# Sheet1.net
KiCad netlist of a schematic drawn in Altium Designer
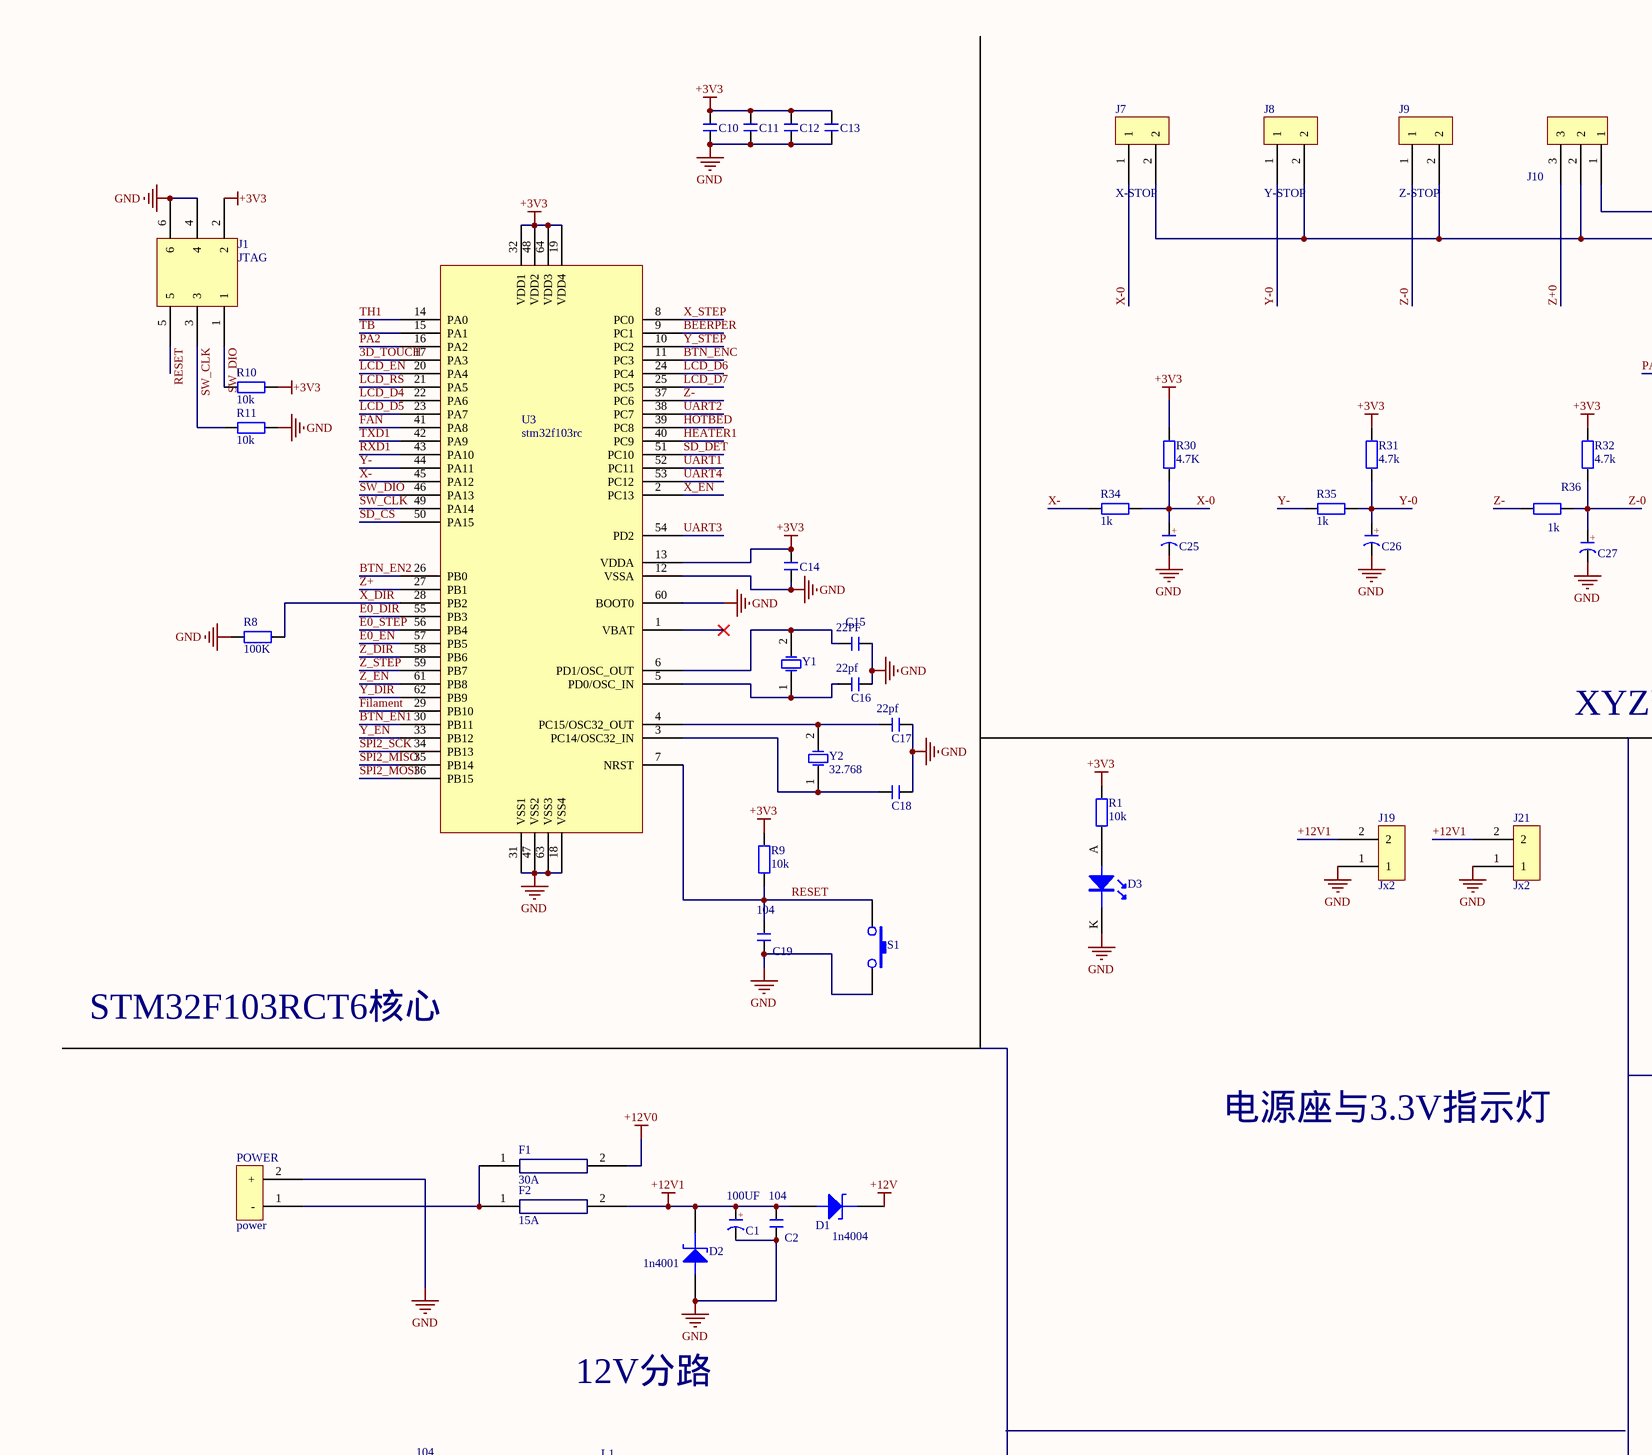
[diagram p0: Sheet1.SchDoc, top left]
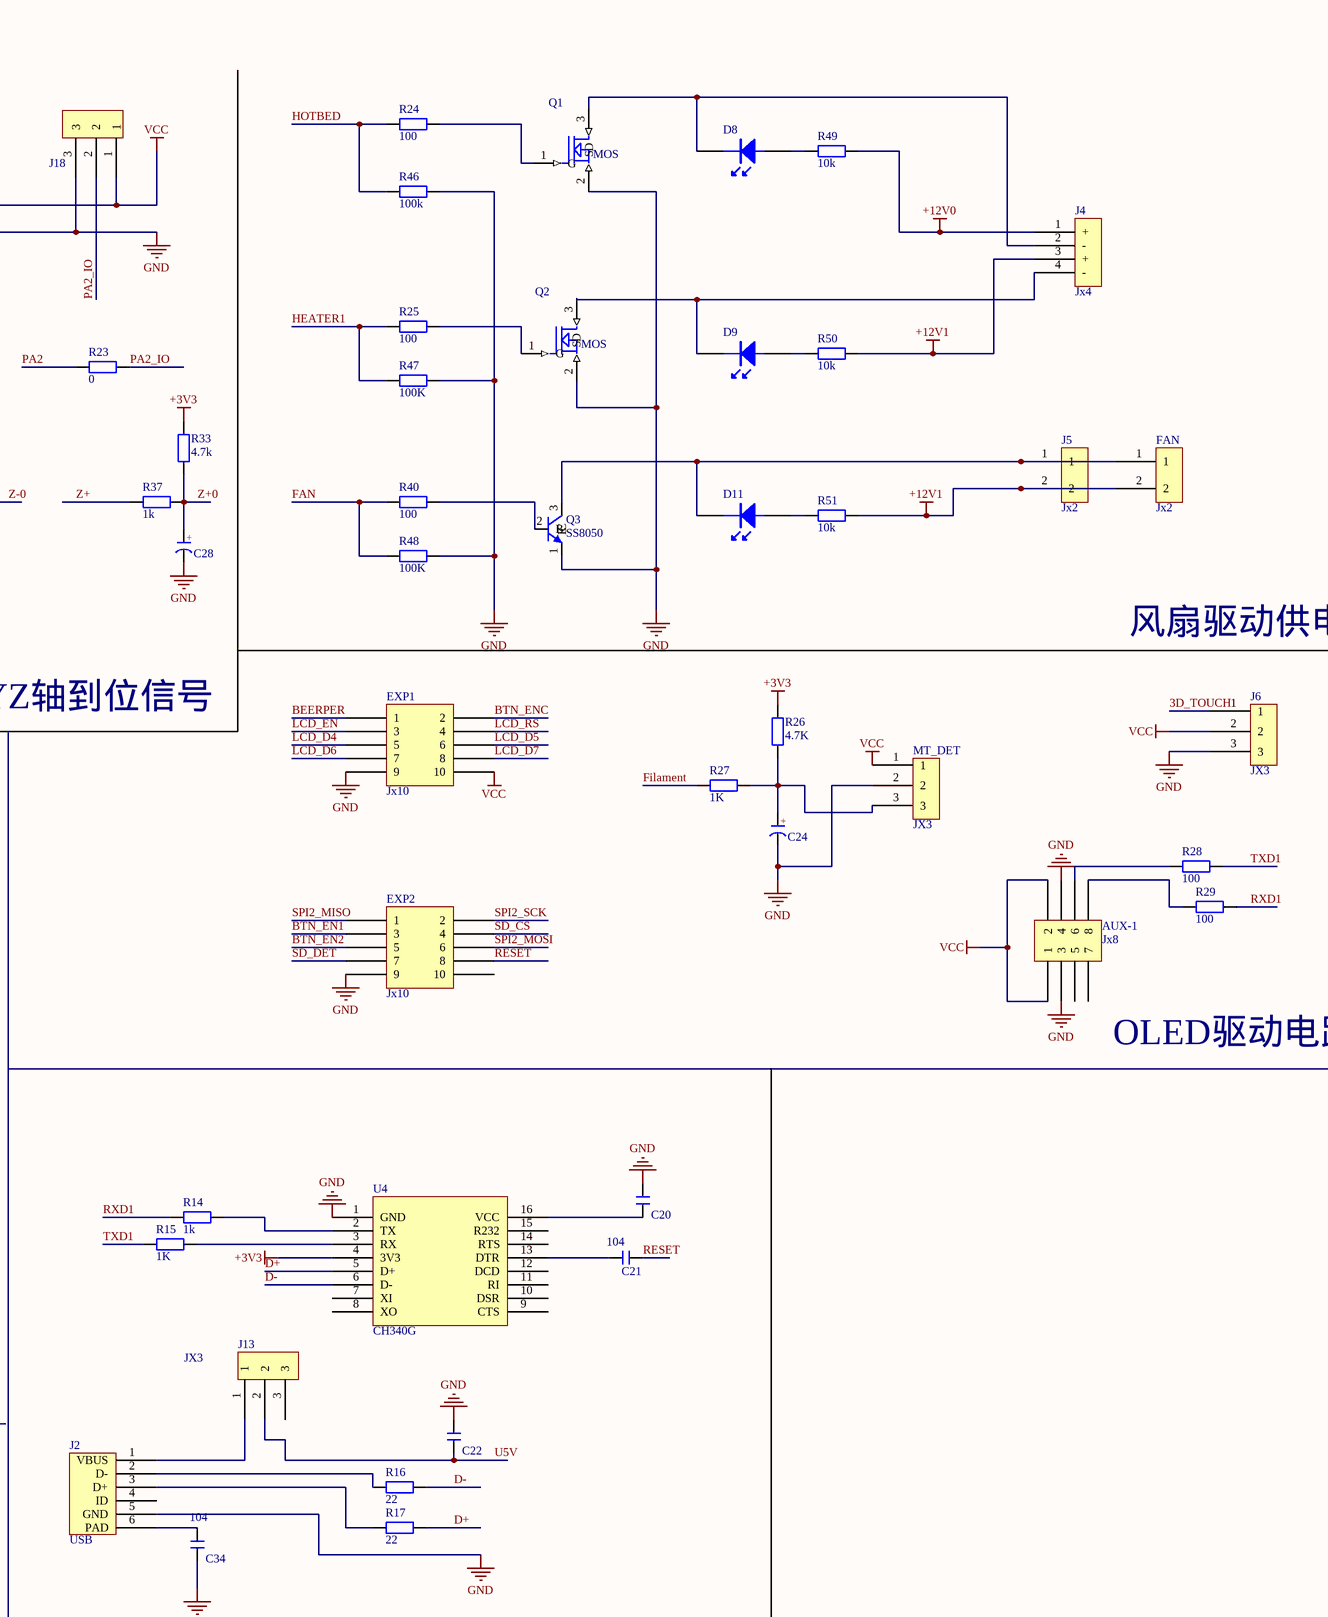
[diagram p1: Sheet1.SchDoc, top middle]
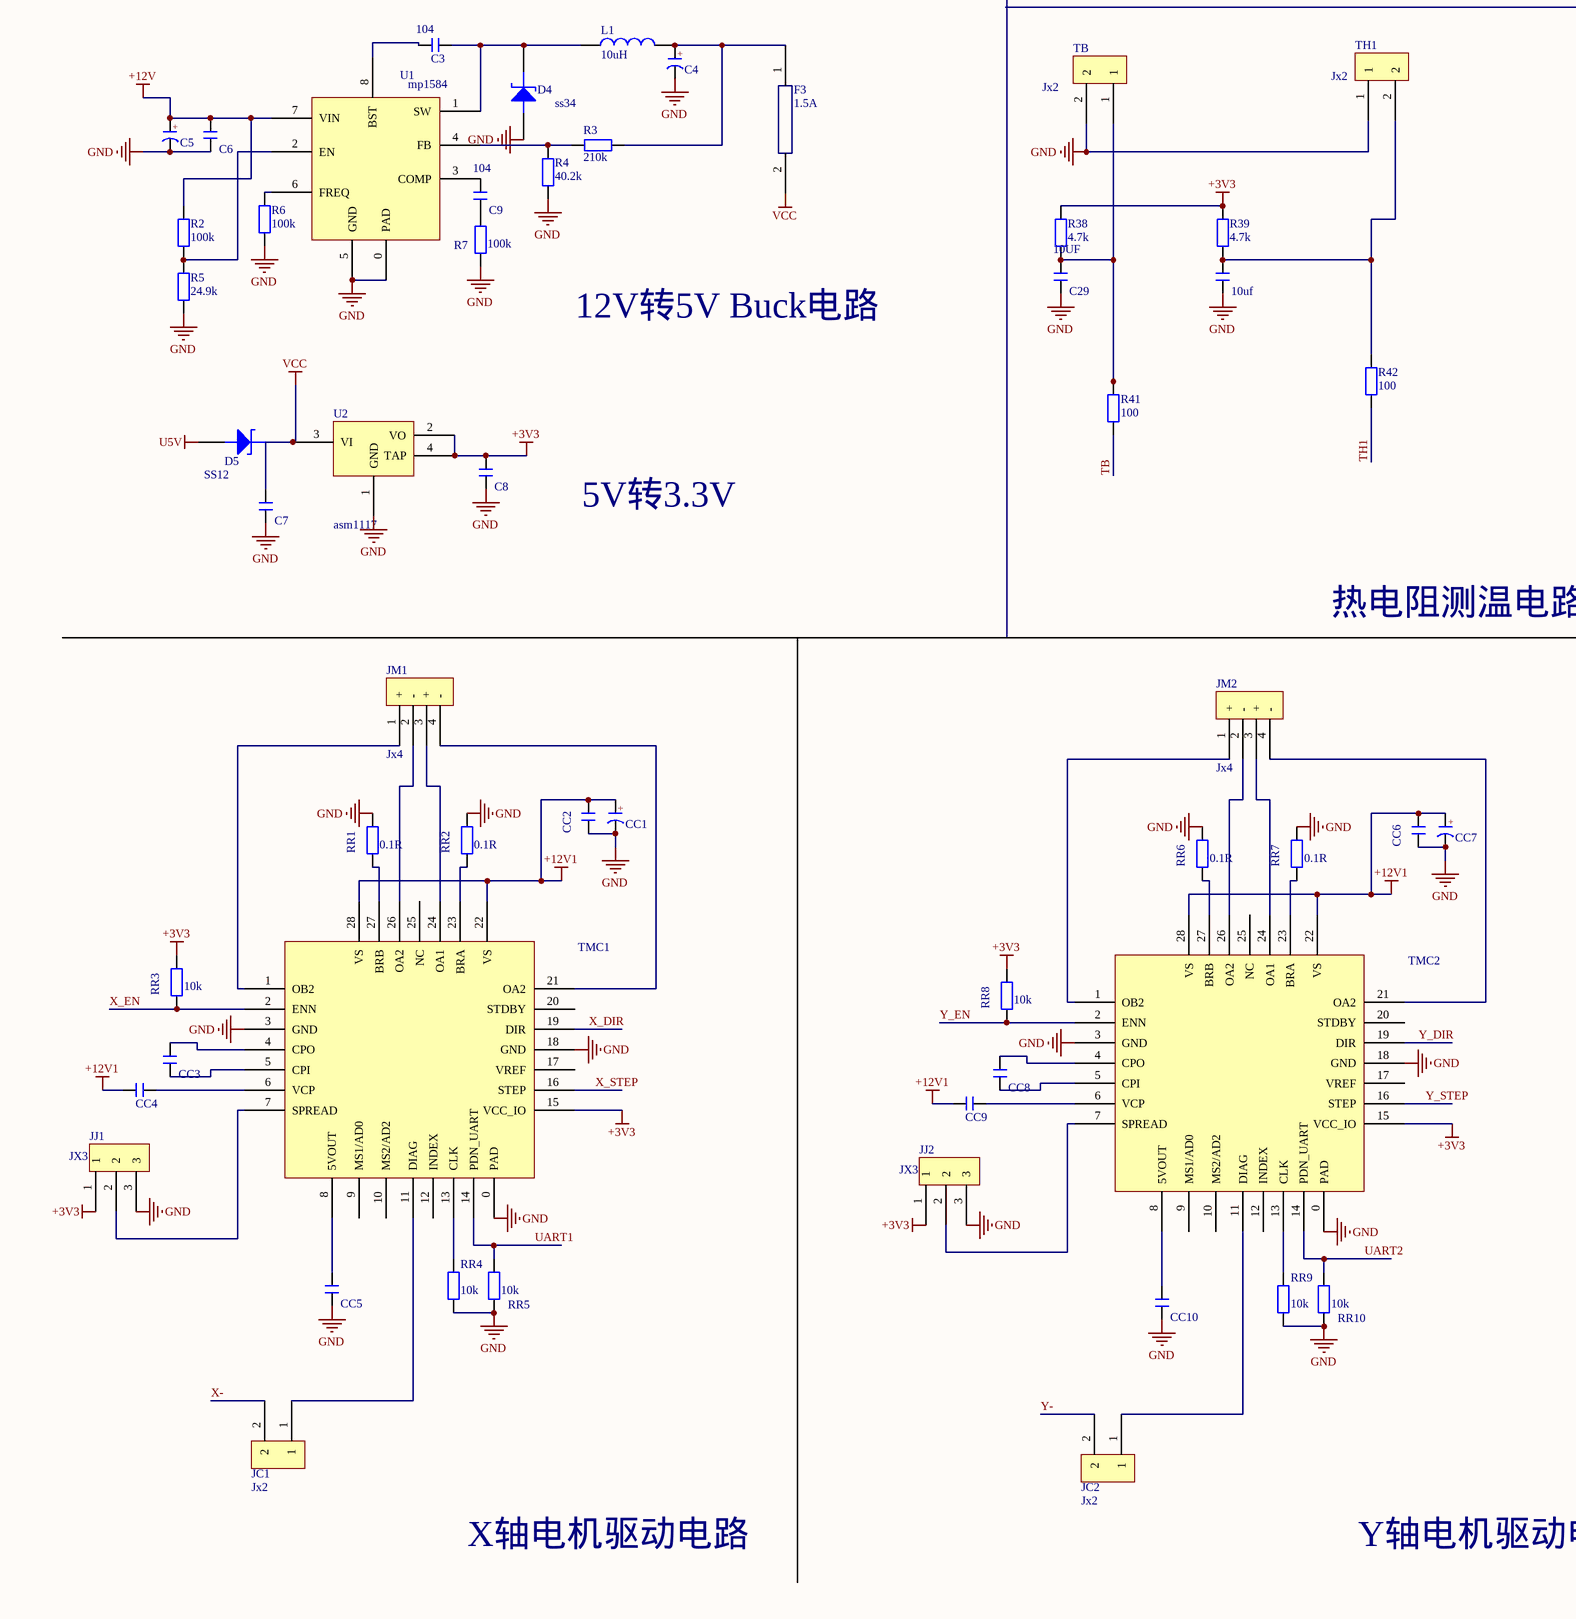
[diagram p2: Sheet1.SchDoc, bottom left]
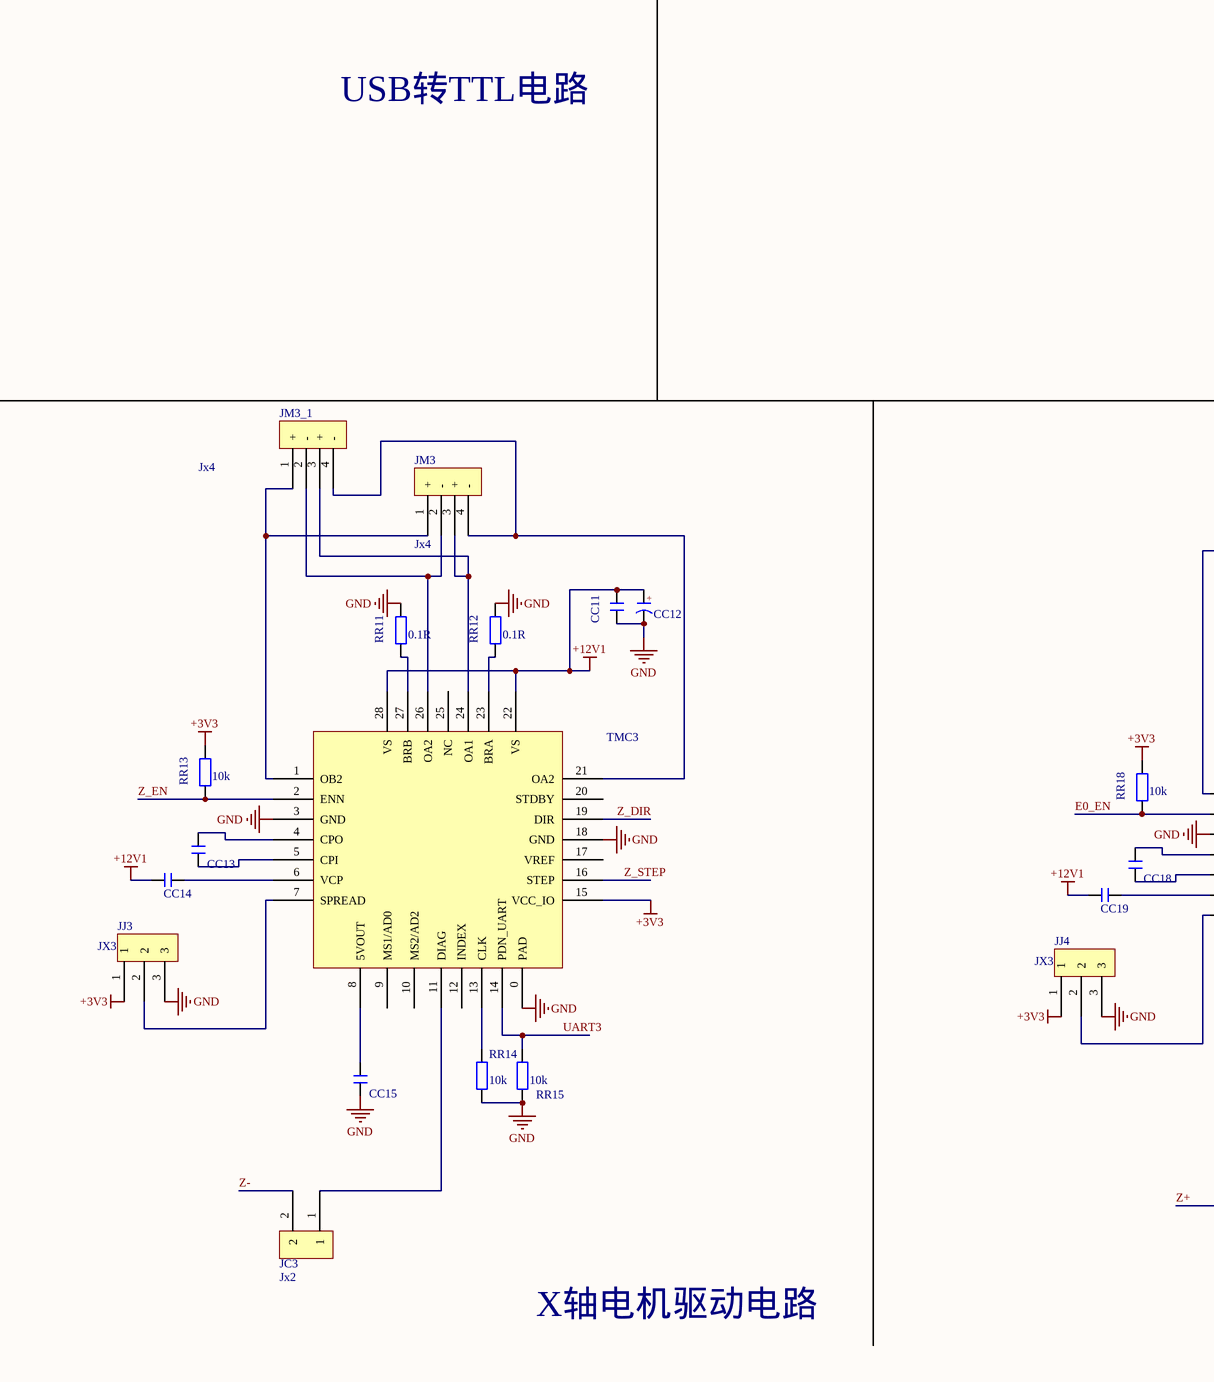
[diagram p3: Sheet1.SchDoc, bottom middle]
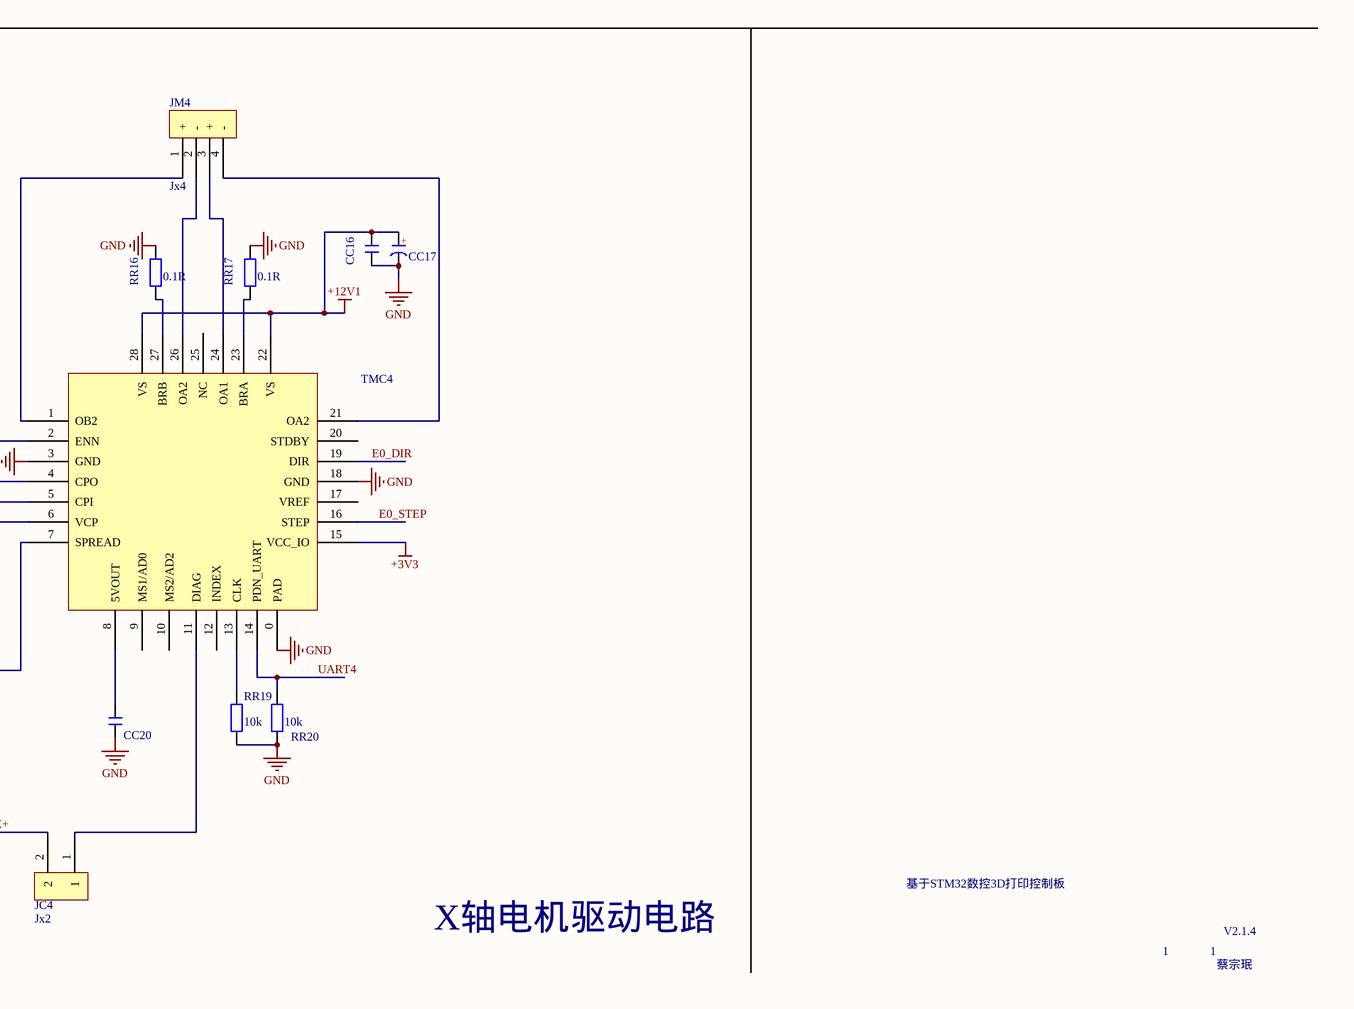
[diagram p4: Sheet1.SchDoc, bottom right]

(export (version "E")
  (design (tool "Eeschema 10.0.6"))
  (components
    (comp (ref "10uf")
      (value "104")
      (footprint "C 0603_M")
      (description "无极性贴片电容")
      (fields (field (name "版权归属") "源创客"))
      (libsource (lib "3.1   - 电阻-电容-电感") (part "C"))
    )
    (comp (ref "AUX-1") (value "Jx8") (footprint "IDC_8P") (libsource (lib "Schlib1") (part "Jx8")))
    (comp (ref "C1")
      (value "100UF")
      (footprint "CS 3.5*8*8 - C")
      (description "贴片电解电容")
      (fields (field (name "版权归属") "源创客"))
      (libsource (lib "3.1   - 电阻-电容-电感") (part "C-CM"))
    )
    (comp (ref "C2")
      (value "104")
      (footprint "C 0603_M")
      (description "无极性贴片电容")
      (fields (field (name "版权归属") "源创客"))
      (libsource (lib "3.1   - 电阻-电容-电感") (part "C"))
    )
    (comp (ref "C3")
      (value "104")
      (footprint "C 0603_M")
      (description "无极性贴片电容")
      (fields (field (name "版权归属") "源创客"))
      (libsource (lib "3.1   - 电阻-电容-电感") (part "C"))
    )
    (comp (ref "C4")
      (value "220uf")
      (footprint "CS 3.5*8*8 - C")
      (description "贴片电解电容")
      (fields (field (name "版权归属") "源创客"))
      (libsource (lib "3.1   - 电阻-电容-电感") (part "C-CM"))
    )
    (comp (ref "C5")
      (value "10uF/10V")
      (footprint "CS 3.5*8*8 - C")
      (description "贴片电解电容")
      (fields (field (name "版权归属") "源创客"))
      (libsource (lib "3.1   - 电阻-电容-电感") (part "C-CM"))
    )
    (comp (ref "C6")
      (value "104")
      (footprint "C 0603_M")
      (description "无极性贴片电容")
      (fields (field (name "版权归属") "源创客"))
      (libsource (lib "3.1   - 电阻-电容-电感") (part "C"))
    )
    (comp (ref "C7")
      (value "10uf")
      (footprint "C 0603_M")
      (description "无极性贴片电容")
      (fields (field (name "版权归属") "源创客"))
      (libsource (lib "3.1   - 电阻-电容-电感") (part "C"))
    )
    (comp (ref "C8")
      (value "10uf")
      (footprint "C 0603_M")
      (description "无极性贴片电容")
      (fields (field (name "版权归属") "源创客"))
      (libsource (lib "3.1   - 电阻-电容-电感") (part "C"))
    )
    (comp (ref "C9")
      (value "104")
      (footprint "C 0603_M")
      (description "无极性贴片电容")
      (fields (field (name "版权归属") "源创客"))
      (libsource (lib "3.1   - 电阻-电容-电感") (part "C"))
    )
    (comp (ref "C10")
      (value "104")
      (footprint "C 0603_M")
      (description "无极性贴片电容")
      (fields (field (name "版权归属") "源创客"))
      (libsource (lib "3.1   - 电阻-电容-电感") (part "C"))
    )
    (comp (ref "C11")
      (value "104")
      (footprint "C 0603_M")
      (description "无极性贴片电容")
      (fields (field (name "版权归属") "源创客"))
      (libsource (lib "3.1   - 电阻-电容-电感") (part "C"))
    )
    (comp (ref "C12")
      (value "104")
      (footprint "C 0603_M")
      (description "无极性贴片电容")
      (fields (field (name "版权归属") "源创客"))
      (libsource (lib "3.1   - 电阻-电容-电感") (part "C"))
    )
    (comp (ref "C13")
      (value "104")
      (footprint "C 0603_M")
      (description "无极性贴片电容")
      (fields (field (name "版权归属") "源创客"))
      (libsource (lib "3.1   - 电阻-电容-电感") (part "C"))
    )
    (comp (ref "C14")
      (value "104")
      (footprint "C 0603_M")
      (description "无极性贴片电容")
      (fields (field (name "版权归属") "源创客"))
      (libsource (lib "3.1   - 电阻-电容-电感") (part "C"))
    )
    (comp (ref "C15")
      (value "22PF")
      (footprint "C 0603_M")
      (description "无极性贴片电容")
      (fields (field (name "版权归属") "源创客"))
      (libsource (lib "3.1   - 电阻-电容-电感") (part "C"))
    )
    (comp (ref "C16")
      (value "22pf")
      (footprint "C 0603_M")
      (description "无极性贴片电容")
      (fields (field (name "版权归属") "源创客"))
      (libsource (lib "3.1   - 电阻-电容-电感") (part "C"))
    )
    (comp (ref "C17")
      (value "22pf")
      (footprint "C 0603_M")
      (description "无极性贴片电容")
      (fields (field (name "版权归属") "源创客"))
      (libsource (lib "3.1   - 电阻-电容-电感") (part "C"))
    )
    (comp (ref "C18")
      (value "22pf")
      (footprint "C 0603_M")
      (description "无极性贴片电容")
      (fields (field (name "版权归属") "源创客"))
      (libsource (lib "3.1   - 电阻-电容-电感") (part "C"))
    )
    (comp (ref "C19")
      (value "104")
      (footprint "C 0603_M")
      (description "无极性贴片电容")
      (fields (field (name "版权归属") "源创客"))
      (libsource (lib "3.1   - 电阻-电容-电感") (part "C"))
    )
    (comp (ref "C20")
      (value "104")
      (footprint "C 0603_M")
      (description "无极性贴片电容")
      (fields (field (name "版权归属") "源创客"))
      (libsource (lib "3.1   - 电阻-电容-电感") (part "C"))
    )
    (comp (ref "C21")
      (value "104")
      (footprint "C 0603_M")
      (description "无极性贴片电容")
      (fields (field (name "版权归属") "源创客"))
      (libsource (lib "3.1   - 电阻-电容-电感") (part "C"))
    )
    (comp (ref "C22")
      (value "104")
      (footprint "C 0603_M")
      (description "无极性贴片电容")
      (fields (field (name "版权归属") "源创客"))
      (libsource (lib "3.1   - 电阻-电容-电感") (part "C"))
    )
    (comp (ref "C24")
      (value "10uF/10V")
      (footprint "C 0603_M")
      (description "贴片电解电容")
      (fields (field (name "版权归属") "源创客"))
      (libsource (lib "3.1   - 电阻-电容-电感") (part "C-CM"))
    )
    (comp (ref "C25")
      (value "10uF/10V")
      (footprint "C 0603_M")
      (description "贴片电解电容")
      (fields (field (name "版权归属") "源创客"))
      (libsource (lib "3.1   - 电阻-电容-电感") (part "C-CM"))
    )
    (comp (ref "C26")
      (value "10uF/10V")
      (footprint "C 0603_M")
      (description "贴片电解电容")
      (fields (field (name "版权归属") "源创客"))
      (libsource (lib "3.1   - 电阻-电容-电感") (part "C-CM"))
    )
    (comp (ref "C27")
      (value "10uF/10V")
      (footprint "C 0603_M")
      (description "贴片电解电容")
      (fields (field (name "版权归属") "源创客"))
      (libsource (lib "3.1   - 电阻-电容-电感") (part "C-CM"))
    )
    (comp (ref "C28")
      (value "10uF/10V")
      (footprint "C 0603_M")
      (description "贴片电解电容")
      (fields (field (name "版权归属") "源创客"))
      (libsource (lib "3.1   - 电阻-电容-电感") (part "C-CM"))
    )
    (comp (ref "C29")
      (value "10UF")
      (footprint "C 0603_M")
      (description "无极性贴片电容")
      (fields (field (name "版权归属") "源创客"))
      (libsource (lib "3.1   - 电阻-电容-电感") (part "C"))
    )
    (comp (ref "C34")
      (value "104")
      (footprint "C 0603_M")
      (description "无极性贴片电容")
      (fields (field (name "版权归属") "源创客"))
      (libsource (lib "3.1   - 电阻-电容-电感") (part "C"))
    )
    (comp (ref "CC1")
      (value "10uF/10V")
      (footprint "C 1206_M")
      (description "贴片电解电容")
      (fields (field (name "版权归属") "源创客"))
      (libsource (lib "3.1   - 电阻-电容-电感") (part "C-CM"))
    )
    (comp (ref "CC2")
      (value "104")
      (footprint "C 0603_M")
      (description "无极性贴片电容")
      (fields (field (name "版权归属") "源创客"))
      (libsource (lib "3.1   - 电阻-电容-电感") (part "C"))
    )
    (comp (ref "CC3")
      (value "104")
      (footprint "C 0603_M")
      (description "无极性贴片电容")
      (fields (field (name "版权归属") "源创客"))
      (libsource (lib "3.1   - 电阻-电容-电感") (part "C"))
    )
    (comp (ref "CC4")
      (value "104")
      (footprint "C 0603_M")
      (description "无极性贴片电容")
      (fields (field (name "版权归属") "源创客"))
      (libsource (lib "3.1   - 电阻-电容-电感") (part "C"))
    )
    (comp (ref "CC5")
      (value "104")
      (footprint "C 0603_M")
      (description "无极性贴片电容")
      (fields (field (name "版权归属") "源创客"))
      (libsource (lib "3.1   - 电阻-电容-电感") (part "C"))
    )
    (comp (ref "CC6")
      (value "104")
      (footprint "C 0603_M")
      (description "无极性贴片电容")
      (fields (field (name "版权归属") "源创客"))
      (libsource (lib "3.1   - 电阻-电容-电感") (part "C"))
    )
    (comp (ref "CC7")
      (value "10uF/10V")
      (footprint "C 1206_M")
      (description "贴片电解电容")
      (fields (field (name "版权归属") "源创客"))
      (libsource (lib "3.1   - 电阻-电容-电感") (part "C-CM"))
    )
    (comp (ref "CC8")
      (value "104")
      (footprint "C 0603_M")
      (description "无极性贴片电容")
      (fields (field (name "版权归属") "源创客"))
      (libsource (lib "3.1   - 电阻-电容-电感") (part "C"))
    )
    (comp (ref "CC9")
      (value "104")
      (footprint "C 0603_M")
      (description "无极性贴片电容")
      (fields (field (name "版权归属") "源创客"))
      (libsource (lib "3.1   - 电阻-电容-电感") (part "C"))
    )
    (comp (ref "CC10")
      (value "104")
      (footprint "C 0603_M")
      (description "无极性贴片电容")
      (fields (field (name "版权归属") "源创客"))
      (libsource (lib "3.1   - 电阻-电容-电感") (part "C"))
    )
    (comp (ref "CC11")
      (value "104")
      (footprint "C 0603_M")
      (description "无极性贴片电容")
      (fields (field (name "版权归属") "源创客"))
      (libsource (lib "3.1   - 电阻-电容-电感") (part "C"))
    )
    (comp (ref "CC12")
      (value "10uF/10V")
      (footprint "C 1206_M")
      (description "贴片电解电容")
      (fields (field (name "版权归属") "源创客"))
      (libsource (lib "3.1   - 电阻-电容-电感") (part "C-CM"))
    )
    (comp (ref "CC13")
      (value "104")
      (footprint "C 0603_M")
      (description "无极性贴片电容")
      (fields (field (name "版权归属") "源创客"))
      (libsource (lib "3.1   - 电阻-电容-电感") (part "C"))
    )
    (comp (ref "CC14")
      (value "104")
      (footprint "C 0603_M")
      (description "无极性贴片电容")
      (fields (field (name "版权归属") "源创客"))
      (libsource (lib "3.1   - 电阻-电容-电感") (part "C"))
    )
    (comp (ref "CC15")
      (value "104")
      (footprint "C 0603_M")
      (description "无极性贴片电容")
      (fields (field (name "版权归属") "源创客"))
      (libsource (lib "3.1   - 电阻-电容-电感") (part "C"))
    )
    (comp (ref "CC16")
      (value "104")
      (footprint "C 0603_M")
      (description "无极性贴片电容")
      (fields (field (name "版权归属") "源创客"))
      (libsource (lib "3.1   - 电阻-电容-电感") (part "C"))
    )
    (comp (ref "CC17")
      (value "10uF/10V")
      (footprint "C 1206_M")
      (description "贴片电解电容")
      (fields (field (name "版权归属") "源创客"))
      (libsource (lib "3.1   - 电阻-电容-电感") (part "C-CM"))
    )
    (comp (ref "CC18")
      (value "104")
      (footprint "C 0603_M")
      (description "无极性贴片电容")
      (fields (field (name "版权归属") "源创客"))
      (libsource (lib "3.1   - 电阻-电容-电感") (part "C"))
    )
    (comp (ref "CC19")
      (value "104")
      (footprint "C 0603_M")
      (description "无极性贴片电容")
      (fields (field (name "版权归属") "源创客"))
      (libsource (lib "3.1   - 电阻-电容-电感") (part "C"))
    )
    (comp (ref "CC20")
      (value "104")
      (footprint "C 0603_M")
      (description "无极性贴片电容")
      (fields (field (name "版权归属") "源创客"))
      (libsource (lib "3.1   - 电阻-电容-电感") (part "C"))
    )
    (comp (ref "D1")
      (value "1n4004")
      (footprint "SMA")
      (description "Zener Diode")
      (libsource (lib "二极管") (part "ZENER2"))
    )
    (comp (ref "D2")
      (value "1n4001")
      (footprint "SMA")
      (description "Zener Diode")
      (libsource (lib "二极管") (part "ZENER2"))
    )
    (comp (ref "D3") (value "发光二极管") (footprint "myLed0805") (libsource (lib "") (part "发光二极管_1")))
    (comp (ref "D4")
      (value "ss34")
      (footprint "SMA")
      (description "Zener Diode")
      (libsource (lib "二极管") (part "ZENER2"))
    )
    (comp (ref "D5")
      (value "SS12")
      (footprint "SMA")
      (description "Zener Diode")
      (libsource (lib "二极管") (part "ZENER2"))
    )
    (comp (ref "D8") (value "发光二极管") (footprint "myLed0805") (libsource (lib "二极管") (part "发光二极管")))
    (comp (ref "D9") (value "发光二极管") (footprint "myLed0805") (libsource (lib "二极管") (part "发光二极管")))
    (comp (ref "D11") (value "发光二极管") (footprint "myLed0805") (libsource (lib "二极管") (part "发光二极管")))
    (comp (ref "EXP1") (value "Jx10") (footprint "DC3-10P") (libsource (lib "Schlib1") (part "Jx10")))
    (comp (ref "EXP2") (value "Jx10") (footprint "DC3-10P") (libsource (lib "Schlib1") (part "Jx10")))
    (comp (ref "F1") (value "30A") (footprint "FU 1206") (libsource (lib "Schlib1") (part "fruse")))
    (comp (ref "F2") (value "15A") (footprint "FU 1206") (libsource (lib "Schlib1") (part "fruse")))
    (comp (ref "F3") (value "1.5A") (footprint "FU 1206") (libsource (lib "Schlib1") (part "fruse")))
    (comp (ref "FAN") (value "Jx2") (footprint "my_XH2.54-2") (libsource (lib "") (part "Jx2_1")))
    (comp (ref "J1") (value "JTAG") (footprint "HDR2.54-LI-2x3P") (libsource (lib "Schlib1") (part "J_2X3")))
    (comp (ref "J2") (value "USB") (footprint "myMicrousb") (libsource (lib "Schlib1") (part "USB")))
    (comp (ref "J4") (value "Jx4") (footprint "HX5.08-4L") (libsource (lib "") (part "Jx4_1")))
    (comp (ref "J5") (value "Jx2") (footprint "my_XH2.54-2") (libsource (lib "") (part "Jx2_1")))
    (comp (ref "J6") (value "JX3") (footprint "HDR2.54-LI-3P") (libsource (lib "Schlib1") (part "JX3")))
    (comp (ref "J7") (value "X-STOP") (footprint "my_XH2.54-2") (libsource (lib "Schlib1") (part "Jx2")))
    (comp (ref "J8") (value "Y-STOP") (footprint "my_XH2.54-2") (libsource (lib "Schlib1") (part "Jx2")))
    (comp (ref "J9") (value "Z-STOP") (footprint "my_XH2.54-2") (libsource (lib "Schlib1") (part "Jx2")))
    (comp (ref "J10") (value "JX3") (footprint "XH_3p") (libsource (lib "Schlib1") (part "JX3")))
    (comp (ref "J13") (value "JX3") (footprint "HDR2.54-LI-3P") (libsource (lib "") (part "JX3_1")))
    (comp (ref "J18") (value "JX3") (footprint "XH_3p") (libsource (lib "Schlib1") (part "JX3")))
    (comp (ref "J19") (value "Jx2") (footprint "my_XH2.54-2") (libsource (lib "Schlib1") (part "Jx2")))
    (comp (ref "J21") (value "Jx2") (footprint "my_XH2.54-2") (libsource (lib "Schlib1") (part "Jx2")))
    (comp (ref "JC1") (value "Jx2") (footprint "HDR2.54-LI-2P") (libsource (lib "") (part "Jx2_2")))
    (comp (ref "JC2") (value "Jx2") (footprint "HDR2.54-LI-2P") (libsource (lib "") (part "Jx2_2")))
    (comp (ref "JC3") (value "Jx2") (footprint "HDR2.54-LI-2P") (libsource (lib "") (part "Jx2_2")))
    (comp (ref "JC4") (value "Jx2") (footprint "HDR2.54-LI-2P") (libsource (lib "") (part "Jx2_2")))
    (comp (ref "JJ1") (value "JX3") (footprint "HDR2.54-LI-3P") (libsource (lib "") (part "JX3_1")))
    (comp (ref "JJ2") (value "JX3") (footprint "HDR2.54-LI-3P") (libsource (lib "") (part "JX3_1")))
    (comp (ref "JJ3") (value "JX3") (footprint "HDR2.54-LI-3P") (libsource (lib "") (part "JX3_1")))
    (comp (ref "JJ4") (value "JX3") (footprint "HDR2.54-LI-3P") (libsource (lib "") (part "JX3_1")))
    (comp (ref "JM1") (value "Jx4") (footprint "XH2.54-4") (libsource (lib "Schlib1") (part "Jx4")))
    (comp (ref "JM2") (value "Jx4") (footprint "XH2.54-4") (libsource (lib "Schlib1") (part "Jx4")))
    (comp (ref "JM3") (value "Jx4") (footprint "XH2.54-4") (libsource (lib "Schlib1") (part "Jx4")))
    (comp (ref "JM3_1") (value "Jx4") (footprint "XH2.54-4") (libsource (lib "Schlib1") (part "Jx4")))
    (comp (ref "JM4") (value "Jx4") (footprint "XH2.54-4") (libsource (lib "Schlib1") (part "Jx4")))
    (comp (ref "L1")
      (value "10uH")
      (footprint "CDRH74")
      (description "小功率贴片电感")
      (fields (field (name "版权归属") "源创客"))
      (libsource (lib "3.1   - 电阻-电容-电感") (part "L"))
    )
    (comp (ref "MT_DET") (value "JX3") (footprint "XH_3p") (libsource (lib "Schlib1") (part "JX3")))
    (comp (ref "POWER") (value "power") (footprint "HX5.08-2L") (libsource (lib "Schlib1") (part "power")))
    (comp (ref "Q1") (value "MOS") (footprint "TO252") (libsource (lib "Schlib1") (part "MOS")))
    (comp (ref "Q2") (value "MOS") (footprint "TO252") (libsource (lib "Schlib1") (part "MOS")))
    (comp (ref "Q3")
      (value "SS8050")
      (footprint "SOT23")
      (description "高频放大-NPN型")
      (fields (field (name "版权归属") "源创客"))
      (libsource (lib "6.2   - 三极管") (part "8050-DIP"))
    )
    (comp (ref "R1")
      (value "10k")
      (footprint "R 0603_M")
      (description "电流检测电阻")
      (fields (field (name "版权归属") "源创客"))
      (libsource (lib "3.1   - 电阻-电容-电感") (part "R-I"))
    )
    (comp (ref "R2")
      (value "100k")
      (footprint "R 0603_M")
      (description "电流检测电阻")
      (fields (field (name "版权归属") "源创客"))
      (libsource (lib "3.1   - 电阻-电容-电感") (part "R-I"))
    )
    (comp (ref "R3")
      (value "210k")
      (footprint "R 0603_M")
      (description "电流检测电阻")
      (fields (field (name "版权归属") "源创客"))
      (libsource (lib "3.1   - 电阻-电容-电感") (part "R-I"))
    )
    (comp (ref "R4")
      (value "40.2k")
      (footprint "R 0603_M")
      (description "电流检测电阻")
      (fields (field (name "版权归属") "源创客"))
      (libsource (lib "3.1   - 电阻-电容-电感") (part "R-I"))
    )
    (comp (ref "R5")
      (value "24.9k")
      (footprint "R 0603_M")
      (description "电流检测电阻")
      (fields (field (name "版权归属") "源创客"))
      (libsource (lib "3.1   - 电阻-电容-电感") (part "R-I"))
    )
    (comp (ref "R6")
      (value "100k")
      (footprint "R 0603_M")
      (description "电流检测电阻")
      (fields (field (name "版权归属") "源创客"))
      (libsource (lib "3.1   - 电阻-电容-电感") (part "R-I"))
    )
    (comp (ref "R7")
      (value "100k")
      (footprint "R 0603_M")
      (description "电流检测电阻")
      (fields (field (name "版权归属") "源创客"))
      (libsource (lib "3.1   - 电阻-电容-电感") (part "R-I"))
    )
    (comp (ref "R8")
      (value "100K")
      (footprint "R 0603_M")
      (description "电流检测电阻")
      (fields (field (name "版权归属") "源创客"))
      (libsource (lib "3.1   - 电阻-电容-电感") (part "R-I"))
    )
    (comp (ref "R9")
      (value "10k")
      (footprint "R 0603_M")
      (description "电流检测电阻")
      (fields (field (name "版权归属") "源创客"))
      (libsource (lib "3.1   - 电阻-电容-电感") (part "R-I"))
    )
    (comp (ref "R10")
      (value "10k")
      (footprint "R 0603_M")
      (description "电流检测电阻")
      (fields (field (name "版权归属") "源创客"))
      (libsource (lib "3.1   - 电阻-电容-电感") (part "R-I"))
    )
    (comp (ref "R11")
      (value "10k")
      (footprint "R 0603_M")
      (description "电流检测电阻")
      (fields (field (name "版权归属") "源创客"))
      (libsource (lib "3.1   - 电阻-电容-电感") (part "R-I"))
    )
    (comp (ref "R14")
      (value "1k")
      (footprint "R 0603_M")
      (description "电流检测电阻")
      (fields (field (name "版权归属") "源创客"))
      (libsource (lib "3.1   - 电阻-电容-电感") (part "R-I"))
    )
    (comp (ref "R15")
      (value "1K")
      (footprint "R 0603_M")
      (description "电流检测电阻")
      (fields (field (name "版权归属") "源创客"))
      (libsource (lib "3.1   - 电阻-电容-电感") (part "R-I"))
    )
    (comp (ref "R16")
      (value "22")
      (footprint "R 0603_M")
      (description "电流检测电阻")
      (fields (field (name "版权归属") "源创客"))
      (libsource (lib "3.1   - 电阻-电容-电感") (part "R-I"))
    )
    (comp (ref "R17")
      (value "22")
      (footprint "R 0603_M")
      (description "电流检测电阻")
      (fields (field (name "版权归属") "源创客"))
      (libsource (lib "3.1   - 电阻-电容-电感") (part "R-I"))
    )
    (comp (ref "R23")
      (value "0")
      (footprint "R 0603_M")
      (description "电流检测电阻")
      (fields (field (name "版权归属") "源创客"))
      (libsource (lib "3.1   - 电阻-电容-电感") (part "R-I"))
    )
    (comp (ref "R24")
      (value "100")
      (footprint "R 0603_M")
      (description "电流检测电阻")
      (fields (field (name "版权归属") "源创客"))
      (libsource (lib "3.1   - 电阻-电容-电感") (part "R-I"))
    )
    (comp (ref "R25")
      (value "100")
      (footprint "R 0603_M")
      (description "电流检测电阻")
      (fields (field (name "版权归属") "源创客"))
      (libsource (lib "3.1   - 电阻-电容-电感") (part "R-I"))
    )
    (comp (ref "R26")
      (value "4.7K")
      (footprint "R 0603_M")
      (description "电流检测电阻")
      (fields (field (name "版权归属") "源创客"))
      (libsource (lib "3.1   - 电阻-电容-电感") (part "R-I"))
    )
    (comp (ref "R27")
      (value "1K")
      (footprint "R 0603_M")
      (description "电流检测电阻")
      (fields (field (name "版权归属") "源创客"))
      (libsource (lib "3.1   - 电阻-电容-电感") (part "R-I"))
    )
    (comp (ref "R28")
      (value "100")
      (footprint "R 0603_M")
      (description "电流检测电阻")
      (fields (field (name "版权归属") "源创客"))
      (libsource (lib "3.1   - 电阻-电容-电感") (part "R-I"))
    )
    (comp (ref "R29")
      (value "100")
      (footprint "R 0603_M")
      (description "电流检测电阻")
      (fields (field (name "版权归属") "源创客"))
      (libsource (lib "3.1   - 电阻-电容-电感") (part "R-I"))
    )
    (comp (ref "R30")
      (value "4.7K")
      (footprint "R 0603_M")
      (description "电流检测电阻")
      (fields (field (name "版权归属") "源创客"))
      (libsource (lib "3.1   - 电阻-电容-电感") (part "R-I"))
    )
    (comp (ref "R31")
      (value "4.7k")
      (footprint "R 0603_M")
      (description "电流检测电阻")
      (fields (field (name "版权归属") "源创客"))
      (libsource (lib "3.1   - 电阻-电容-电感") (part "R-I"))
    )
    (comp (ref "R32")
      (value "4.7k")
      (footprint "R 0603_M")
      (description "电流检测电阻")
      (fields (field (name "版权归属") "源创客"))
      (libsource (lib "3.1   - 电阻-电容-电感") (part "R-I"))
    )
    (comp (ref "R33")
      (value "4.7k")
      (footprint "R 0603_M")
      (description "电流检测电阻")
      (fields (field (name "版权归属") "源创客"))
      (libsource (lib "3.1   - 电阻-电容-电感") (part "R-I"))
    )
    (comp (ref "R34")
      (value "1k")
      (footprint "R 0603_M")
      (description "电流检测电阻")
      (fields (field (name "版权归属") "源创客"))
      (libsource (lib "3.1   - 电阻-电容-电感") (part "R-I"))
    )
    (comp (ref "R35")
      (value "1k")
      (footprint "R 0603_M")
      (description "电流检测电阻")
      (fields (field (name "版权归属") "源创客"))
      (libsource (lib "3.1   - 电阻-电容-电感") (part "R-I"))
    )
    (comp (ref "R36")
      (value "1k")
      (footprint "R 0603_M")
      (description "电流检测电阻")
      (fields (field (name "版权归属") "源创客"))
      (libsource (lib "3.1   - 电阻-电容-电感") (part "R-I"))
    )
    (comp (ref "R37")
      (value "1k")
      (footprint "R 0603_M")
      (description "电流检测电阻")
      (fields (field (name "版权归属") "源创客"))
      (libsource (lib "3.1   - 电阻-电容-电感") (part "R-I"))
    )
    (comp (ref "R38")
      (value "4.7k")
      (footprint "R 0603_M")
      (description "电流检测电阻")
      (fields (field (name "版权归属") "源创客"))
      (libsource (lib "3.1   - 电阻-电容-电感") (part "R-I"))
    )
    (comp (ref "R39")
      (value "4.7k")
      (footprint "R 0603_M")
      (description "电流检测电阻")
      (fields (field (name "版权归属") "源创客"))
      (libsource (lib "3.1   - 电阻-电容-电感") (part "R-I"))
    )
    (comp (ref "R40")
      (value "100")
      (footprint "R 0603_M")
      (description "电流检测电阻")
      (fields (field (name "版权归属") "源创客"))
      (libsource (lib "3.1   - 电阻-电容-电感") (part "R-I"))
    )
    (comp (ref "R41")
      (value "100")
      (footprint "R 0603_M")
      (description "电流检测电阻")
      (fields (field (name "版权归属") "源创客"))
      (libsource (lib "3.1   - 电阻-电容-电感") (part "R-I"))
    )
    (comp (ref "R42")
      (value "100")
      (footprint "R 0603_M")
      (description "电流检测电阻")
      (fields (field (name "版权归属") "源创客"))
      (libsource (lib "3.1   - 电阻-电容-电感") (part "R-I"))
    )
    (comp (ref "R46")
      (value "100k")
      (footprint "R 0603_M")
      (description "电流检测电阻")
      (fields (field (name "版权归属") "源创客"))
      (libsource (lib "3.1   - 电阻-电容-电感") (part "R-I"))
    )
    (comp (ref "R47")
      (value "100K")
      (footprint "R 0603_M")
      (description "电流检测电阻")
      (fields (field (name "版权归属") "源创客"))
      (libsource (lib "3.1   - 电阻-电容-电感") (part "R-I"))
    )
    (comp (ref "R48")
      (value "100K")
      (footprint "R 0603_M")
      (description "电流检测电阻")
      (fields (field (name "版权归属") "源创客"))
      (libsource (lib "3.1   - 电阻-电容-电感") (part "R-I"))
    )
    (comp (ref "R49")
      (value "10k")
      (footprint "R 0603_M")
      (description "电流检测电阻")
      (fields (field (name "版权归属") "源创客"))
      (libsource (lib "3.1   - 电阻-电容-电感") (part "R-I"))
    )
    (comp (ref "R50")
      (value "10k")
      (footprint "R 0603_M")
      (description "电流检测电阻")
      (fields (field (name "版权归属") "源创客"))
      (libsource (lib "3.1   - 电阻-电容-电感") (part "R-I"))
    )
    (comp (ref "R51")
      (value "10k")
      (footprint "R 0603_M")
      (description "电流检测电阻")
      (fields (field (name "版权归属") "源创客"))
      (libsource (lib "3.1   - 电阻-电容-电感") (part "R-I"))
    )
    (comp (ref "RR1")
      (value "0.1R")
      (footprint "R 1206_L")
      (description "电流检测电阻")
      (fields (field (name "版权归属") "源创客"))
      (libsource (lib "3.1   - 电阻-电容-电感") (part "R-I"))
    )
    (comp (ref "RR2")
      (value "0.1R")
      (footprint "R 1206_L")
      (description "电流检测电阻")
      (fields (field (name "版权归属") "源创客"))
      (libsource (lib "3.1   - 电阻-电容-电感") (part "R-I"))
    )
    (comp (ref "RR3")
      (value "10k")
      (footprint "R 0603_M")
      (description "电流检测电阻")
      (fields (field (name "版权归属") "源创客"))
      (libsource (lib "3.1   - 电阻-电容-电感") (part "R-I"))
    )
    (comp (ref "RR4")
      (value "10k")
      (footprint "R 0603_M")
      (description "电流检测电阻")
      (fields (field (name "版权归属") "源创客"))
      (libsource (lib "3.1   - 电阻-电容-电感") (part "R-I"))
    )
    (comp (ref "RR5")
      (value "10k")
      (footprint "R 0603_M")
      (description "电流检测电阻")
      (fields (field (name "版权归属") "源创客"))
      (libsource (lib "3.1   - 电阻-电容-电感") (part "R-I"))
    )
    (comp (ref "RR6")
      (value "0.1R")
      (footprint "R 1206_L")
      (description "电流检测电阻")
      (fields (field (name "版权归属") "源创客"))
      (libsource (lib "3.1   - 电阻-电容-电感") (part "R-I"))
    )
    (comp (ref "RR7")
      (value "0.1R")
      (footprint "R 1206_L")
      (description "电流检测电阻")
      (fields (field (name "版权归属") "源创客"))
      (libsource (lib "3.1   - 电阻-电容-电感") (part "R-I"))
    )
    (comp (ref "RR8")
      (value "10k")
      (footprint "R 0603_M")
      (description "电流检测电阻")
      (fields (field (name "版权归属") "源创客"))
      (libsource (lib "3.1   - 电阻-电容-电感") (part "R-I"))
    )
    (comp (ref "RR9")
      (value "10k")
      (footprint "R 0603_M")
      (description "电流检测电阻")
      (fields (field (name "版权归属") "源创客"))
      (libsource (lib "3.1   - 电阻-电容-电感") (part "R-I"))
    )
    (comp (ref "RR10")
      (value "10k")
      (footprint "R 0603_M")
      (description "电流检测电阻")
      (fields (field (name "版权归属") "源创客"))
      (libsource (lib "3.1   - 电阻-电容-电感") (part "R-I"))
    )
    (comp (ref "RR11")
      (value "0.1R")
      (footprint "R 1206_L")
      (description "电流检测电阻")
      (fields (field (name "版权归属") "源创客"))
      (libsource (lib "3.1   - 电阻-电容-电感") (part "R-I"))
    )
    (comp (ref "RR12")
      (value "0.1R")
      (footprint "R 1206_L")
      (description "电流检测电阻")
      (fields (field (name "版权归属") "源创客"))
      (libsource (lib "3.1   - 电阻-电容-电感") (part "R-I"))
    )
    (comp (ref "RR13")
      (value "10k")
      (footprint "R 0603_M")
      (description "电流检测电阻")
      (fields (field (name "版权归属") "源创客"))
      (libsource (lib "3.1   - 电阻-电容-电感") (part "R-I"))
    )
    (comp (ref "RR14")
      (value "10k")
      (footprint "R 0603_M")
      (description "电流检测电阻")
      (fields (field (name "版权归属") "源创客"))
      (libsource (lib "3.1   - 电阻-电容-电感") (part "R-I"))
    )
    (comp (ref "RR15")
      (value "10k")
      (footprint "R 0603_M")
      (description "电流检测电阻")
      (fields (field (name "版权归属") "源创客"))
      (libsource (lib "3.1   - 电阻-电容-电感") (part "R-I"))
    )
    (comp (ref "RR16")
      (value "0.1R")
      (footprint "R 1206_L")
      (description "电流检测电阻")
      (fields (field (name "版权归属") "源创客"))
      (libsource (lib "3.1   - 电阻-电容-电感") (part "R-I"))
    )
    (comp (ref "RR17")
      (value "0.1R")
      (footprint "R 1206_L")
      (description "电流检测电阻")
      (fields (field (name "版权归属") "源创客"))
      (libsource (lib "3.1   - 电阻-电容-电感") (part "R-I"))
    )
    (comp (ref "RR18")
      (value "10k")
      (footprint "R 0603_M")
      (description "电流检测电阻")
      (fields (field (name "版权归属") "源创客"))
      (libsource (lib "3.1   - 电阻-电容-电感") (part "R-I"))
    )
    (comp (ref "RR19")
      (value "10k")
      (footprint "R 0603_M")
      (description "电流检测电阻")
      (fields (field (name "版权归属") "源创客"))
      (libsource (lib "3.1   - 电阻-电容-电感") (part "R-I"))
    )
    (comp (ref "RR20")
      (value "10k")
      (footprint "R 0603_M")
      (description "电流检测电阻")
      (fields (field (name "版权归属") "源创客"))
      (libsource (lib "3.1   - 电阻-电容-电感") (part "R-I"))
    )
    (comp (ref "S1") (value "微动开关") (footprint "TSW SMD-3*6*2.5") (libsource (lib "开关") (part "微动开关")))
    (comp (ref "TB") (value "Jx2") (footprint "my_XH2.54-2") (libsource (lib "") (part "Jx2_1")))
    (comp (ref "TH1") (value "Jx2") (footprint "my_XH2.54-2") (libsource (lib "Schlib1") (part "Jx2")))
    (comp (ref "TMC1") (value "TMC2208") (footprint "my_2208") (libsource (lib "Schlib1") (part "TMC2208")))
    (comp (ref "TMC2") (value "TMC2208") (footprint "my_2208") (libsource (lib "Schlib1") (part "TMC2208")))
    (comp (ref "TMC3") (value "TMC2208") (footprint "my_2208") (libsource (lib "Schlib1") (part "TMC2208")))
    (comp (ref "TMC4") (value "TMC2208") (footprint "my_2208") (libsource (lib "Schlib1") (part "TMC2208")))
    (comp (ref "U1") (value "mp1584") (footprint "MP1584EN") (libsource (lib "Schlib1") (part "mp1584")))
    (comp (ref "U2") (value "asm1117") (footprint "SOT-223") (libsource (lib "Schlib1") (part "asm1117")))
    (comp (ref "U3")
      (value "stm32f103rc")
      (footprint "LQFP64_M")
      (libsource (lib "Schlib1") (part "STM32_F103RC"))
    )
    (comp (ref "U4") (value "CH340G") (footprint "SOP16") (libsource (lib "Schlib1") (part "CH340G")))
    (comp (ref "Y1")
      (value "8MHz")
      (footprint "OSC HC-49S")
      (description "Crystal Oscillator")
      (fields (field (name "PUBLISHER") "Altium Limited"))
      (libsource (lib "WarShip V3 STM32103封装库") (part "XTAL"))
    )
    (comp (ref "Y2")
      (value "32.768")
      (footprint "OSC-3x8-LI")
      (description "Crystal Oscillator")
      (fields (field (name "PUBLISHER") "Altium Limited"))
      (libsource (lib "WarShip V3 STM32103封装库") (part "XTAL"))
    )
  )
  (nets
    (net (code "1") (name "+3V3") (class "Default")
      (node (ref "C10") (pin "2") (pinfunction "2_2") (pintype "passive"))
      (node (ref "C11") (pin "2") (pinfunction "2_2") (pintype "passive"))
      (node (ref "C12") (pin "2") (pinfunction "2_2") (pintype "passive"))
      (node (ref "C13") (pin "2") (pinfunction "2_2") (pintype "passive"))
      (node (ref "C14") (pin "2") (pinfunction "2_2") (pintype "passive"))
      (node (ref "C8") (pin "1") (pinfunction "1_1") (pintype "passive"))
      (node (ref "J1") (pin "2") (pinfunction "2_2") (pintype "passive"))
      (node (ref "JJ1") (pin "1") (pinfunction "1_1") (pintype "passive"))
      (node (ref "JJ2") (pin "1") (pinfunction "1_1") (pintype "passive"))
      (node (ref "JJ3") (pin "1") (pinfunction "1_1") (pintype "passive"))
      (node (ref "JJ4") (pin "1") (pinfunction "1_1") (pintype "passive"))
      (node (ref "R1") (pin "2") (pinfunction "2_2") (pintype "passive"))
      (node (ref "R10") (pin "1") (pinfunction "1_1") (pintype "passive"))
      (node (ref "R26") (pin "1") (pinfunction "1_1") (pintype "passive"))
      (node (ref "R30") (pin "2") (pinfunction "2_2") (pintype "passive"))
      (node (ref "R31") (pin "2") (pinfunction "2_2") (pintype "passive"))
      (node (ref "R32") (pin "2") (pinfunction "2_2") (pintype "passive"))
      (node (ref "R33") (pin "2") (pinfunction "2_2") (pintype "passive"))
      (node (ref "R38") (pin "1") (pinfunction "1_1") (pintype "passive"))
      (node (ref "R39") (pin "1") (pinfunction "1_1") (pintype "passive"))
      (node (ref "R9") (pin "2") (pinfunction "2_2") (pintype "passive"))
      (node (ref "RR13") (pin "2") (pinfunction "2_2") (pintype "passive"))
      (node (ref "RR18") (pin "2") (pinfunction "2_2") (pintype "passive"))
      (node (ref "RR3") (pin "2") (pinfunction "2_2") (pintype "passive"))
      (node (ref "RR8") (pin "2") (pinfunction "2_2") (pintype "passive"))
      (node (ref "TMC1") (pin "15") (pinfunction "VCC_IO_15") (pintype "passive"))
      (node (ref "TMC2") (pin "15") (pinfunction "VCC_IO_15") (pintype "passive"))
      (node (ref "TMC3") (pin "15") (pinfunction "VCC_IO_15") (pintype "passive"))
      (node (ref "TMC4") (pin "15") (pinfunction "VCC_IO_15") (pintype "passive"))
      (node (ref "U2") (pin "2") (pinfunction "VO_2") (pintype "passive"))
      (node (ref "U2") (pin "4") (pinfunction "TAP_4") (pintype "passive"))
      (node (ref "U3") (pin "13") (pinfunction "VDDA_13") (pintype "passive"))
      (node (ref "U3") (pin "19") (pinfunction "VDD4_19") (pintype "passive"))
      (node (ref "U3") (pin "32") (pinfunction "VDD1_32") (pintype "passive"))
      (node (ref "U3") (pin "48") (pinfunction "VDD2_48") (pintype "passive"))
      (node (ref "U3") (pin "64") (pinfunction "VDD3_64") (pintype "passive"))
      (node (ref "U4") (pin "4") (pinfunction "3V3_4") (pintype "passive"))
    )
    (net (code "2") (name "+12V") (class "Default")
      (node (ref "C5") (pin "1") (pinfunction "A_1") (pintype "passive"))
      (node (ref "C6") (pin "1") (pinfunction "1_1") (pintype "passive"))
      (node (ref "D1") (pin "2") (pinfunction "K_2") (pintype "passive"))
      (node (ref "R2") (pin "2") (pinfunction "2_2") (pintype "passive"))
      (node (ref "U1") (pin "7") (pinfunction "VIN_7") (pintype "passive"))
    )
    (net (code "3") (name "+12V0") (class "Default")
      (node (ref "F1") (pin "2") (pinfunction "+_2") (pintype "passive"))
      (node (ref "J4") (pin "1") (pinfunction "+_1") (pintype "passive"))
      (node (ref "R49") (pin "1") (pinfunction "1_1") (pintype "passive"))
    )
    (net (code "4") (name "+12V1") (class "Default")
      (node (ref "C1") (pin "1") (pinfunction "A_1") (pintype "passive"))
      (node (ref "C2") (pin "1") (pinfunction "1_1") (pintype "passive"))
      (node (ref "CC1") (pin "1") (pinfunction "A_1") (pintype "passive"))
      (node (ref "CC11") (pin "1") (pinfunction "1_1") (pintype "passive"))
      (node (ref "CC12") (pin "1") (pinfunction "A_1") (pintype "passive"))
      (node (ref "CC14") (pin "2") (pinfunction "2_2") (pintype "passive"))
      (node (ref "CC16") (pin "1") (pinfunction "1_1") (pintype "passive"))
      (node (ref "CC17") (pin "1") (pinfunction "A_1") (pintype "passive"))
      (node (ref "CC19") (pin "2") (pinfunction "2_2") (pintype "passive"))
      (node (ref "CC2") (pin "1") (pinfunction "1_1") (pintype "passive"))
      (node (ref "CC4") (pin "2") (pinfunction "2_2") (pintype "passive"))
      (node (ref "CC6") (pin "1") (pinfunction "1_1") (pintype "passive"))
      (node (ref "CC7") (pin "1") (pinfunction "A_1") (pintype "passive"))
      (node (ref "CC9") (pin "2") (pinfunction "2_2") (pintype "passive"))
      (node (ref "D1") (pin "1") (pinfunction "A_1") (pintype "passive"))
      (node (ref "D2") (pin "2") (pinfunction "K_2") (pintype "passive"))
      (node (ref "F2") (pin "2") (pinfunction "+_2") (pintype "passive"))
      (node (ref "FAN") (pin "2") (pinfunction "2_2") (pintype "passive"))
      (node (ref "J19") (pin "2") (pinfunction "2_2") (pintype "passive"))
      (node (ref "J21") (pin "2") (pinfunction "2_2") (pintype "passive"))
      (node (ref "J4") (pin "3") (pinfunction "+_3") (pintype "passive"))
      (node (ref "J5") (pin "2") (pinfunction "2_2") (pintype "passive"))
      (node (ref "R50") (pin "1") (pinfunction "1_1") (pintype "passive"))
      (node (ref "R51") (pin "1") (pinfunction "1_1") (pintype "passive"))
      (node (ref "TMC1") (pin "22") (pinfunction "VS_22") (pintype "passive"))
      (node (ref "TMC1") (pin "28") (pinfunction "VS_28") (pintype "passive"))
      (node (ref "TMC2") (pin "22") (pinfunction "VS_22") (pintype "passive"))
      (node (ref "TMC2") (pin "28") (pinfunction "VS_28") (pintype "passive"))
      (node (ref "TMC3") (pin "22") (pinfunction "VS_22") (pintype "passive"))
      (node (ref "TMC3") (pin "28") (pinfunction "VS_28") (pintype "passive"))
      (node (ref "TMC4") (pin "22") (pinfunction "VS_22") (pintype "passive"))
      (node (ref "TMC4") (pin "28") (pinfunction "VS_28") (pintype "passive"))
    )
    (net (code "5") (name "/3D_TOUCH") (class "Default")
      (node (ref "J6") (pin "1") (pinfunction "1_1") (pintype "passive"))
      (node (ref "U3") (pin "17") (pinfunction "PA3_17") (pintype "passive"))
    )
    (net (code "6") (name "/BEERPER") (class "Default")
      (node (ref "EXP1") (pin "1") (pinfunction "1_1") (pintype "passive"))
      (node (ref "U3") (pin "9") (pinfunction "PC1_9") (pintype "passive"))
    )
    (net (code "7") (name "/BTN_EN1") (class "Default")
      (node (ref "EXP2") (pin "3") (pinfunction "3_3") (pintype "passive"))
      (node (ref "U3") (pin "30") (pinfunction "PB11_30") (pintype "passive"))
    )
    (net (code "8") (name "/BTN_EN2") (class "Default")
      (node (ref "EXP2") (pin "5") (pinfunction "5_5") (pintype "passive"))
      (node (ref "U3") (pin "26") (pinfunction "PB0_26") (pintype "passive"))
    )
    (net (code "9") (name "/BTN_ENC") (class "Default")
      (node (ref "EXP1") (pin "2") (pinfunction "2_2") (pintype "passive"))
      (node (ref "U3") (pin "11") (pinfunction "PC3_11") (pintype "passive"))
    )
    (net (code "10") (name "/D+") (class "Default")
      (node (ref "R17") (pin "1") (pinfunction "1_1") (pintype "passive"))
      (node (ref "U4") (pin "5") (pinfunction "D+_5") (pintype "passive"))
    )
    (net (code "11") (name "/D-") (class "Default")
      (node (ref "R16") (pin "1") (pinfunction "1_1") (pintype "passive"))
      (node (ref "U4") (pin "6") (pinfunction "D-_6") (pintype "passive"))
    )
    (net (code "12") (name "/E0_DIR") (class "Default")
      (node (ref "TMC4") (pin "19") (pinfunction "DIR_19") (pintype "passive"))
      (node (ref "U3") (pin "55") (pinfunction "PB3_55") (pintype "passive"))
    )
    (net (code "13") (name "/E0_EN") (class "Default")
      (node (ref "RR18") (pin "1") (pinfunction "1_1") (pintype "passive"))
      (node (ref "TMC4") (pin "2") (pinfunction "ENN_2") (pintype "passive"))
      (node (ref "U3") (pin "57") (pinfunction "PB5_57") (pintype "passive"))
    )
    (net (code "14") (name "/E0_STEP") (class "Default")
      (node (ref "TMC4") (pin "16") (pinfunction "STEP_16") (pintype "passive"))
      (node (ref "U3") (pin "56") (pinfunction "PB4_56") (pintype "passive"))
    )
    (net (code "15") (name "/FAN") (class "Default")
      (node (ref "R40") (pin "2") (pinfunction "2_2") (pintype "passive"))
      (node (ref "R48") (pin "2") (pinfunction "2_2") (pintype "passive"))
      (node (ref "U3") (pin "41") (pinfunction "PA8_41") (pintype "passive"))
    )
    (net (code "16") (name "/Filament") (class "Default")
      (node (ref "R27") (pin "2") (pinfunction "2_2") (pintype "passive"))
      (node (ref "U3") (pin "29") (pinfunction "PB10_29") (pintype "passive"))
    )
    (net (code "17") (name "/HEATER1") (class "Default")
      (node (ref "R25") (pin "2") (pinfunction "2_2") (pintype "passive"))
      (node (ref "R47") (pin "2") (pinfunction "2_2") (pintype "passive"))
      (node (ref "U3") (pin "40") (pinfunction "PC9_40") (pintype "passive"))
    )
    (net (code "18") (name "/HOTBED") (class "Default")
      (node (ref "R24") (pin "2") (pinfunction "2_2") (pintype "passive"))
      (node (ref "R46") (pin "2") (pinfunction "2_2") (pintype "passive"))
      (node (ref "U3") (pin "39") (pinfunction "PC8_39") (pintype "passive"))
    )
    (net (code "19") (name "/LCD_D4") (class "Default")
      (node (ref "EXP1") (pin "5") (pinfunction "5_5") (pintype "passive"))
      (node (ref "U3") (pin "22") (pinfunction "PA6_22") (pintype "passive"))
    )
    (net (code "20") (name "/LCD_D5") (class "Default")
      (node (ref "EXP1") (pin "6") (pinfunction "6_6") (pintype "passive"))
      (node (ref "U3") (pin "23") (pinfunction "PA7_23") (pintype "passive"))
    )
    (net (code "21") (name "/LCD_D6") (class "Default")
      (node (ref "EXP1") (pin "7") (pinfunction "7_7") (pintype "passive"))
      (node (ref "U3") (pin "24") (pinfunction "PC4_24") (pintype "passive"))
    )
    (net (code "22") (name "/LCD_D7") (class "Default")
      (node (ref "EXP1") (pin "8") (pinfunction "8_8") (pintype "passive"))
      (node (ref "U3") (pin "25") (pinfunction "PC5_25") (pintype "passive"))
    )
    (net (code "23") (name "/LCD_EN") (class "Default")
      (node (ref "EXP1") (pin "3") (pinfunction "3_3") (pintype "passive"))
      (node (ref "U3") (pin "20") (pinfunction "PA4_20") (pintype "passive"))
    )
    (net (code "24") (name "/LCD_RS") (class "Default")
      (node (ref "EXP1") (pin "4") (pinfunction "4_4") (pintype "passive"))
      (node (ref "U3") (pin "21") (pinfunction "PA5_21") (pintype "passive"))
    )
    (net (code "25") (name "/PA2") (class "Default")
      (node (ref "R23") (pin "2") (pinfunction "2_2") (pintype "passive"))
      (node (ref "U3") (pin "16") (pinfunction "PA2_16") (pintype "passive"))
    )
    (net (code "26") (name "/PA2_IO") (class "Default")
      (node (ref "J18") (pin "2") (pinfunction "2_2") (pintype "passive"))
      (node (ref "R23") (pin "1") (pinfunction "1_1") (pintype "passive"))
    )
    (net (code "27") (name "/RESET") (class "Default")
      (node (ref "C19") (pin "1") (pinfunction "1_1") (pintype "passive"))
      (node (ref "C21") (pin "2") (pinfunction "2_2") (pintype "passive"))
      (node (ref "EXP2") (pin "8") (pinfunction "8_8") (pintype "passive"))
      (node (ref "J1") (pin "5") (pinfunction "5_5") (pintype "passive"))
      (node (ref "R9") (pin "1") (pinfunction "1_1") (pintype "passive"))
      (node (ref "S1") (pin "1") (pinfunction "1_1") (pintype "passive"))
      (node (ref "U3") (pin "7") (pinfunction "NRST_7") (pintype "passive"))
    )
    (net (code "28") (name "/RXD1") (class "Default")
      (node (ref "R14") (pin "2") (pinfunction "2_2") (pintype "passive"))
      (node (ref "R29") (pin "1") (pinfunction "1_1") (pintype "passive"))
      (node (ref "U3") (pin "43") (pinfunction "PA10_43") (pintype "passive"))
    )
    (net (code "29") (name "/SD_CS") (class "Default")
      (node (ref "EXP2") (pin "4") (pinfunction "4_4") (pintype "passive"))
      (node (ref "U3") (pin "50") (pinfunction "PA15_50") (pintype "passive"))
    )
    (net (code "30") (name "/SD_DET") (class "Default")
      (node (ref "EXP2") (pin "7") (pinfunction "7_7") (pintype "passive"))
      (node (ref "U3") (pin "51") (pinfunction "PC10_51") (pintype "passive"))
    )
    (net (code "31") (name "/SPI2_MISO") (class "Default")
      (node (ref "EXP2") (pin "1") (pinfunction "1_1") (pintype "passive"))
      (node (ref "U3") (pin "35") (pinfunction "PB14_35") (pintype "passive"))
    )
    (net (code "32") (name "/SPI2_MOSI") (class "Default")
      (node (ref "EXP2") (pin "6") (pinfunction "6_6") (pintype "passive"))
      (node (ref "U3") (pin "36") (pinfunction "PB15_36") (pintype "passive"))
    )
    (net (code "33") (name "/SPI2_SCK") (class "Default")
      (node (ref "EXP2") (pin "2") (pinfunction "2_2") (pintype "passive"))
      (node (ref "U3") (pin "34") (pinfunction "PB13_34") (pintype "passive"))
    )
    (net (code "34") (name "/SW_CLK") (class "Default")
      (node (ref "J1") (pin "3") (pinfunction "3_3") (pintype "passive"))
      (node (ref "R11") (pin "2") (pinfunction "2_2") (pintype "passive"))
      (node (ref "U3") (pin "49") (pinfunction "PA14_49") (pintype "passive"))
    )
    (net (code "35") (name "/SW_DIO") (class "Default")
      (node (ref "J1") (pin "1") (pinfunction "1_1") (pintype "passive"))
      (node (ref "R10") (pin "2") (pinfunction "2_2") (pintype "passive"))
      (node (ref "U3") (pin "46") (pinfunction "PA13_46") (pintype "passive"))
    )
    (net (code "36") (name "/TB") (class "Default")
      (node (ref "R41") (pin "2") (pinfunction "2_2") (pintype "passive"))
      (node (ref "U3") (pin "15") (pinfunction "PA1_15") (pintype "passive"))
    )
    (net (code "37") (name "/TH1") (class "Default")
      (node (ref "R42") (pin "2") (pinfunction "2_2") (pintype "passive"))
      (node (ref "U3") (pin "14") (pinfunction "PA0_14") (pintype "passive"))
    )
    (net (code "38") (name "/TXD1") (class "Default")
      (node (ref "R15") (pin "2") (pinfunction "2_2") (pintype "passive"))
      (node (ref "R28") (pin "1") (pinfunction "1_1") (pintype "passive"))
      (node (ref "U3") (pin "42") (pinfunction "PA9_42") (pintype "passive"))
    )
    (net (code "39") (name "/UART1") (class "Default")
      (node (ref "RR5") (pin "2") (pinfunction "2_2") (pintype "passive"))
      (node (ref "TMC1") (pin "14") (pinfunction "PDN_UART_14") (pintype "passive"))
      (node (ref "U3") (pin "52") (pinfunction "PC11_52") (pintype "passive"))
    )
    (net (code "40") (name "/UART2") (class "Default")
      (node (ref "RR10") (pin "2") (pinfunction "2_2") (pintype "passive"))
      (node (ref "TMC2") (pin "14") (pinfunction "PDN_UART_14") (pintype "passive"))
      (node (ref "U3") (pin "38") (pinfunction "PC7_38") (pintype "passive"))
    )
    (net (code "41") (name "/UART3") (class "Default")
      (node (ref "RR15") (pin "2") (pinfunction "2_2") (pintype "passive"))
      (node (ref "TMC3") (pin "14") (pinfunction "PDN_UART_14") (pintype "passive"))
      (node (ref "U3") (pin "54") (pinfunction "PD2_54") (pintype "passive"))
    )
    (net (code "42") (name "/UART4") (class "Default")
      (node (ref "RR20") (pin "2") (pinfunction "2_2") (pintype "passive"))
      (node (ref "TMC4") (pin "14") (pinfunction "PDN_UART_14") (pintype "passive"))
      (node (ref "U3") (pin "53") (pinfunction "PC12_53") (pintype "passive"))
    )
    (net (code "43") (name "/X-") (class "Default")
      (node (ref "JC1") (pin "2") (pinfunction "2_2") (pintype "passive"))
      (node (ref "R34") (pin "2") (pinfunction "2_2") (pintype "passive"))
      (node (ref "U3") (pin "45") (pinfunction "PA12_45") (pintype "passive"))
    )
    (net (code "44") (name "/X-0") (class "Default")
      (node (ref "C25") (pin "1") (pinfunction "A_1") (pintype "passive"))
      (node (ref "J7") (pin "1") (pinfunction "1_1") (pintype "passive"))
      (node (ref "R30") (pin "1") (pinfunction "1_1") (pintype "passive"))
      (node (ref "R34") (pin "1") (pinfunction "1_1") (pintype "passive"))
    )
    (net (code "45") (name "/X_DIR") (class "Default")
      (node (ref "R8") (pin "1") (pinfunction "1_1") (pintype "passive"))
      (node (ref "TMC1") (pin "19") (pinfunction "DIR_19") (pintype "passive"))
      (node (ref "U3") (pin "28") (pinfunction "PB2_28") (pintype "passive"))
    )
    (net (code "46") (name "/X_EN") (class "Default")
      (node (ref "RR3") (pin "1") (pinfunction "1_1") (pintype "passive"))
      (node (ref "TMC1") (pin "2") (pinfunction "ENN_2") (pintype "passive"))
      (node (ref "U3") (pin "2") (pinfunction "PC13_2") (pintype "passive"))
    )
    (net (code "47") (name "/X_STEP") (class "Default")
      (node (ref "TMC1") (pin "16") (pinfunction "STEP_16") (pintype "passive"))
      (node (ref "U3") (pin "8") (pinfunction "PC0_8") (pintype "passive"))
    )
    (net (code "48") (name "/Y-") (class "Default")
      (node (ref "JC2") (pin "2") (pinfunction "2_2") (pintype "passive"))
      (node (ref "R35") (pin "2") (pinfunction "2_2") (pintype "passive"))
      (node (ref "U3") (pin "44") (pinfunction "PA11_44") (pintype "passive"))
    )
    (net (code "49") (name "/Y-0") (class "Default")
      (node (ref "C26") (pin "1") (pinfunction "A_1") (pintype "passive"))
      (node (ref "J8") (pin "1") (pinfunction "1_1") (pintype "passive"))
      (node (ref "R31") (pin "1") (pinfunction "1_1") (pintype "passive"))
      (node (ref "R35") (pin "1") (pinfunction "1_1") (pintype "passive"))
    )
    (net (code "50") (name "/Y_DIR") (class "Default")
      (node (ref "TMC2") (pin "19") (pinfunction "DIR_19") (pintype "passive"))
      (node (ref "U3") (pin "62") (pinfunction "PB9_62") (pintype "passive"))
    )
    (net (code "51") (name "/Y_EN") (class "Default")
      (node (ref "RR8") (pin "1") (pinfunction "1_1") (pintype "passive"))
      (node (ref "TMC2") (pin "2") (pinfunction "ENN_2") (pintype "passive"))
      (node (ref "U3") (pin "33") (pinfunction "PB12_33") (pintype "passive"))
    )
    (net (code "52") (name "/Y_STEP") (class "Default")
      (node (ref "TMC2") (pin "16") (pinfunction "STEP_16") (pintype "passive"))
      (node (ref "U3") (pin "10") (pinfunction "PC2_10") (pintype "passive"))
    )
    (net (code "53") (name "/Z+") (class "Default")
      (node (ref "JC4") (pin "2") (pinfunction "2_2") (pintype "passive"))
      (node (ref "R37") (pin "2") (pinfunction "2_2") (pintype "passive"))
      (node (ref "U3") (pin "27") (pinfunction "PB1_27") (pintype "passive"))
    )
    (net (code "54") (name "/Z+0") (class "Default")
      (node (ref "C28") (pin "1") (pinfunction "A_1") (pintype "passive"))
      (node (ref "J10") (pin "3") (pinfunction "3_3") (pintype "passive"))
      (node (ref "R33") (pin "1") (pinfunction "1_1") (pintype "passive"))
      (node (ref "R37") (pin "1") (pinfunction "1_1") (pintype "passive"))
    )
    (net (code "55") (name "/Z-") (class "Default")
      (node (ref "JC3") (pin "2") (pinfunction "2_2") (pintype "passive"))
      (node (ref "R36") (pin "2") (pinfunction "2_2") (pintype "passive"))
      (node (ref "U3") (pin "37") (pinfunction "PC6_37") (pintype "passive"))
    )
    (net (code "56") (name "/Z-0") (class "Default")
      (node (ref "C27") (pin "1") (pinfunction "A_1") (pintype "passive"))
      (node (ref "J9") (pin "1") (pinfunction "1_1") (pintype "passive"))
      (node (ref "R32") (pin "1") (pinfunction "1_1") (pintype "passive"))
      (node (ref "R36") (pin "1") (pinfunction "1_1") (pintype "passive"))
    )
    (net (code "57") (name "/Z_DIR") (class "Default")
      (node (ref "TMC3") (pin "19") (pinfunction "DIR_19") (pintype "passive"))
      (node (ref "U3") (pin "58") (pinfunction "PB6_58") (pintype "passive"))
    )
    (net (code "58") (name "/Z_EN") (class "Default")
      (node (ref "RR13") (pin "1") (pinfunction "1_1") (pintype "passive"))
      (node (ref "TMC3") (pin "2") (pinfunction "ENN_2") (pintype "passive"))
      (node (ref "U3") (pin "61") (pinfunction "PB8_61") (pintype "passive"))
    )
    (net (code "59") (name "/Z_STEP") (class "Default")
      (node (ref "TMC3") (pin "16") (pinfunction "STEP_16") (pintype "passive"))
      (node (ref "U3") (pin "59") (pinfunction "PB7_59") (pintype "passive"))
    )
    (net (code "60") (name "GND") (class "Default")
      (node (ref "10uf") (pin "2") (pinfunction "2_2") (pintype "passive"))
      (node (ref "AUX-1") (pin "3") (pinfunction "3_3") (pintype "passive"))
      (node (ref "AUX-1") (pin "4") (pinfunction "4_4") (pintype "passive"))
      (node (ref "C1") (pin "2") (pinfunction "K_2") (pintype "passive"))
      (node (ref "C10") (pin "1") (pinfunction "1_1") (pintype "passive"))
      (node (ref "C11") (pin "1") (pinfunction "1_1") (pintype "passive"))
      (node (ref "C12") (pin "1") (pinfunction "1_1") (pintype "passive"))
      (node (ref "C13") (pin "1") (pinfunction "1_1") (pintype "passive"))
      (node (ref "C14") (pin "1") (pinfunction "1_1") (pintype "passive"))
      (node (ref "C15") (pin "1") (pinfunction "1_1") (pintype "passive"))
      (node (ref "C16") (pin "1") (pinfunction "1_1") (pintype "passive"))
      (node (ref "C17") (pin "1") (pinfunction "1_1") (pintype "passive"))
      (node (ref "C18") (pin "1") (pinfunction "1_1") (pintype "passive"))
      (node (ref "C19") (pin "2") (pinfunction "2_2") (pintype "passive"))
      (node (ref "C2") (pin "2") (pinfunction "2_2") (pintype "passive"))
      (node (ref "C20") (pin "1") (pinfunction "1_1") (pintype "passive"))
      (node (ref "C22") (pin "2") (pinfunction "2_2") (pintype "passive"))
      (node (ref "C24") (pin "2") (pinfunction "K_2") (pintype "passive"))
      (node (ref "C25") (pin "2") (pinfunction "K_2") (pintype "passive"))
      (node (ref "C26") (pin "2") (pinfunction "K_2") (pintype "passive"))
      (node (ref "C27") (pin "2") (pinfunction "K_2") (pintype "passive"))
      (node (ref "C28") (pin "2") (pinfunction "K_2") (pintype "passive"))
      (node (ref "C29") (pin "2") (pinfunction "2_2") (pintype "passive"))
      (node (ref "C34") (pin "1") (pinfunction "1_1") (pintype "passive"))
      (node (ref "C4") (pin "2") (pinfunction "K_2") (pintype "passive"))
      (node (ref "C5") (pin "2") (pinfunction "K_2") (pintype "passive"))
      (node (ref "C6") (pin "2") (pinfunction "2_2") (pintype "passive"))
      (node (ref "C7") (pin "2") (pinfunction "2_2") (pintype "passive"))
      (node (ref "C8") (pin "2") (pinfunction "2_2") (pintype "passive"))
      (node (ref "CC1") (pin "2") (pinfunction "K_2") (pintype "passive"))
      (node (ref "CC10") (pin "2") (pinfunction "2_2") (pintype "passive"))
      (node (ref "CC11") (pin "2") (pinfunction "2_2") (pintype "passive"))
      (node (ref "CC12") (pin "2") (pinfunction "K_2") (pintype "passive"))
      (node (ref "CC15") (pin "2") (pinfunction "2_2") (pintype "passive"))
      (node (ref "CC16") (pin "2") (pinfunction "2_2") (pintype "passive"))
      (node (ref "CC17") (pin "2") (pinfunction "K_2") (pintype "passive"))
      (node (ref "CC2") (pin "2") (pinfunction "2_2") (pintype "passive"))
      (node (ref "CC20") (pin "2") (pinfunction "2_2") (pintype "passive"))
      (node (ref "CC5") (pin "2") (pinfunction "2_2") (pintype "passive"))
      (node (ref "CC6") (pin "2") (pinfunction "2_2") (pintype "passive"))
      (node (ref "CC7") (pin "2") (pinfunction "K_2") (pintype "passive"))
      (node (ref "D2") (pin "1") (pinfunction "A_1") (pintype "passive"))
      (node (ref "D3") (pin "K") (pinfunction "K_K") (pintype "passive"))
      (node (ref "D4") (pin "1") (pinfunction "A_1") (pintype "passive"))
      (node (ref "EXP1") (pin "9") (pinfunction "9_9") (pintype "passive"))
      (node (ref "EXP2") (pin "9") (pinfunction "9_9") (pintype "passive"))
      (node (ref "J1") (pin "4") (pinfunction "4_4") (pintype "passive"))
      (node (ref "J1") (pin "6") (pinfunction "6_6") (pintype "passive"))
      (node (ref "J10") (pin "2") (pinfunction "2_2") (pintype "passive"))
      (node (ref "J18") (pin "3") (pinfunction "3_3") (pintype "passive"))
      (node (ref "J19") (pin "1") (pinfunction "1_1") (pintype "passive"))
      (node (ref "J2") (pin "5") (pinfunction "GND_5") (pintype "passive"))
      (node (ref "J21") (pin "1") (pinfunction "1_1") (pintype "passive"))
      (node (ref "J6") (pin "3") (pinfunction "3_3") (pintype "passive"))
      (node (ref "J7") (pin "2") (pinfunction "2_2") (pintype "passive"))
      (node (ref "J8") (pin "2") (pinfunction "2_2") (pintype "passive"))
      (node (ref "J9") (pin "2") (pinfunction "2_2") (pintype "passive"))
      (node (ref "JJ1") (pin "3") (pinfunction "3_3") (pintype "passive"))
      (node (ref "JJ2") (pin "3") (pinfunction "3_3") (pintype "passive"))
      (node (ref "JJ3") (pin "3") (pinfunction "3_3") (pintype "passive"))
      (node (ref "JJ4") (pin "3") (pinfunction "3_3") (pintype "passive"))
      (node (ref "MT_DET") (pin "2") (pinfunction "2_2") (pintype "passive"))
      (node (ref "POWER") (pin "2") (pinfunction "+_2") (pintype "passive"))
      (node (ref "Q1") (pin "2") (pinfunction "S_2") (pintype "input"))
      (node (ref "Q2") (pin "2") (pinfunction "S_2") (pintype "input"))
      (node (ref "Q3") (pin "1") (pinfunction "E_1") (pintype "passive"))
      (node (ref "R11") (pin "1") (pinfunction "1_1") (pintype "passive"))
      (node (ref "R4") (pin "1") (pinfunction "1_1") (pintype "passive"))
      (node (ref "R46") (pin "1") (pinfunction "1_1") (pintype "passive"))
      (node (ref "R47") (pin "1") (pinfunction "1_1") (pintype "passive"))
      (node (ref "R48") (pin "1") (pinfunction "1_1") (pintype "passive"))
      (node (ref "R5") (pin "1") (pinfunction "1_1") (pintype "passive"))
      (node (ref "R6") (pin "1") (pinfunction "1_1") (pintype "passive"))
      (node (ref "R7") (pin "1") (pinfunction "1_1") (pintype "passive"))
      (node (ref "R8") (pin "2") (pinfunction "2_2") (pintype "passive"))
      (node (ref "RR1") (pin "2") (pinfunction "2_2") (pintype "passive"))
      (node (ref "RR10") (pin "1") (pinfunction "1_1") (pintype "passive"))
      (node (ref "RR11") (pin "2") (pinfunction "2_2") (pintype "passive"))
      (node (ref "RR12") (pin "2") (pinfunction "2_2") (pintype "passive"))
      (node (ref "RR14") (pin "1") (pinfunction "1_1") (pintype "passive"))
      (node (ref "RR15") (pin "1") (pinfunction "1_1") (pintype "passive"))
      (node (ref "RR16") (pin "2") (pinfunction "2_2") (pintype "passive"))
      (node (ref "RR17") (pin "2") (pinfunction "2_2") (pintype "passive"))
      (node (ref "RR19") (pin "1") (pinfunction "1_1") (pintype "passive"))
      (node (ref "RR2") (pin "2") (pinfunction "2_2") (pintype "passive"))
      (node (ref "RR20") (pin "1") (pinfunction "1_1") (pintype "passive"))
      (node (ref "RR4") (pin "1") (pinfunction "1_1") (pintype "passive"))
      (node (ref "RR5") (pin "1") (pinfunction "1_1") (pintype "passive"))
      (node (ref "RR6") (pin "2") (pinfunction "2_2") (pintype "passive"))
      (node (ref "RR7") (pin "2") (pinfunction "2_2") (pintype "passive"))
      (node (ref "RR9") (pin "1") (pinfunction "1_1") (pintype "passive"))
      (node (ref "S1") (pin "2") (pinfunction "2_2") (pintype "passive"))
      (node (ref "TB") (pin "2") (pinfunction "2_2") (pintype "passive"))
      (node (ref "TH1") (pin "1") (pinfunction "1_1") (pintype "passive"))
      (node (ref "TMC1") (pin "0") (pinfunction "PAD_0") (pintype "passive"))
      (node (ref "TMC1") (pin "18") (pinfunction "GND_18") (pintype "passive"))
      (node (ref "TMC1") (pin "3") (pinfunction "GND_3") (pintype "passive"))
      (node (ref "TMC2") (pin "0") (pinfunction "PAD_0") (pintype "passive"))
      (node (ref "TMC2") (pin "18") (pinfunction "GND_18") (pintype "passive"))
      (node (ref "TMC2") (pin "3") (pinfunction "GND_3") (pintype "passive"))
      (node (ref "TMC3") (pin "0") (pinfunction "PAD_0") (pintype "passive"))
      (node (ref "TMC3") (pin "18") (pinfunction "GND_18") (pintype "passive"))
      (node (ref "TMC3") (pin "3") (pinfunction "GND_3") (pintype "passive"))
      (node (ref "TMC4") (pin "0") (pinfunction "PAD_0") (pintype "passive"))
      (node (ref "TMC4") (pin "18") (pinfunction "GND_18") (pintype "passive"))
      (node (ref "TMC4") (pin "3") (pinfunction "GND_3") (pintype "passive"))
      (node (ref "U1") (pin "0") (pinfunction "PAD_0") (pintype "passive"))
      (node (ref "U1") (pin "5") (pinfunction "GND_5") (pintype "passive"))
      (node (ref "U2") (pin "1") (pinfunction "GND_1") (pintype "passive"))
      (node (ref "U3") (pin "12") (pinfunction "VSSA_12") (pintype "passive"))
      (node (ref "U3") (pin "18") (pinfunction "VSS4_18") (pintype "passive"))
      (node (ref "U3") (pin "31") (pinfunction "VSS1_31") (pintype "passive"))
      (node (ref "U3") (pin "47") (pinfunction "VSS2_47") (pintype "passive"))
      (node (ref "U3") (pin "60") (pinfunction "BOOT0_60") (pintype "passive"))
      (node (ref "U3") (pin "63") (pinfunction "VSS3_63") (pintype "passive"))
      (node (ref "U4") (pin "1") (pinfunction "GND_1") (pintype "passive"))
    )
    (net (code "61") (name "Net-(10uf-Pad1)") (class "Default")
      (node (ref "10uf") (pin "1") (pinfunction "1_1") (pintype "passive"))
      (node (ref "R39") (pin "2") (pinfunction "2_2") (pintype "passive"))
      (node (ref "R42") (pin "1") (pinfunction "1_1") (pintype "passive"))
      (node (ref "TH1") (pin "2") (pinfunction "2_2") (pintype "passive"))
    )
    (net (code "62") (name "Net-(AUX-1-Pad6)") (class "Default")
      (node (ref "AUX-1") (pin "6") (pinfunction "6_6") (pintype "passive"))
      (node (ref "R28") (pin "2") (pinfunction "2_2") (pintype "passive"))
    )
    (net (code "63") (name "Net-(AUX-1-Pad8)") (class "Default")
      (node (ref "AUX-1") (pin "8") (pinfunction "8_8") (pintype "passive"))
      (node (ref "R29") (pin "2") (pinfunction "2_2") (pintype "passive"))
    )
    (net (code "64") (name "Net-(C4-A)") (class "Default")
      (node (ref "C4") (pin "1") (pinfunction "A_1") (pintype "passive"))
      (node (ref "F3") (pin "1") (pinfunction "+_1") (pintype "passive"))
      (node (ref "L1") (pin "2") (pinfunction "2_2") (pintype "passive"))
      (node (ref "R3") (pin "1") (pinfunction "1_1") (pintype "passive"))
    )
    (net (code "65") (name "Net-(C9-Pad2)") (class "Default")
      (node (ref "C9") (pin "2") (pinfunction "2_2") (pintype "passive"))
      (node (ref "R7") (pin "2") (pinfunction "2_2") (pintype "passive"))
    )
    (net (code "66") (name "Net-(C24-A)") (class "Default")
      (node (ref "C24") (pin "1") (pinfunction "A_1") (pintype "passive"))
      (node (ref "MT_DET") (pin "3") (pinfunction "3_3") (pintype "passive"))
      (node (ref "R26") (pin "2") (pinfunction "2_2") (pintype "passive"))
      (node (ref "R27") (pin "1") (pinfunction "1_1") (pintype "passive"))
    )
    (net (code "67") (name "Net-(C29-Pad1)") (class "Default")
      (node (ref "C29") (pin "1") (pinfunction "1_1") (pintype "passive"))
      (node (ref "R38") (pin "2") (pinfunction "2_2") (pintype "passive"))
      (node (ref "R41") (pin "1") (pinfunction "1_1") (pintype "passive"))
      (node (ref "TB") (pin "1") (pinfunction "1_1") (pintype "passive"))
    )
    (net (code "68") (name "Net-(D3-PadA)") (class "Default")
      (node (ref "D3") (pin "A") (pinfunction "A_A") (pintype "passive"))
      (node (ref "R1") (pin "1") (pinfunction "1_1") (pintype "passive"))
    )
    (net (code "69") (name "Net-(D4-K)") (class "Default")
      (node (ref "C3") (pin "2") (pinfunction "2_2") (pintype "passive"))
      (node (ref "D4") (pin "2") (pinfunction "K_2") (pintype "passive"))
      (node (ref "L1") (pin "1") (pinfunction "1_1") (pintype "passive"))
      (node (ref "U1") (pin "1") (pinfunction "SW_1") (pintype "passive"))
    )
    (net (code "70") (name "Net-(D8-1)") (class "Default")
      (node (ref "D8") (pin "A") (pinfunction "1_A") (pintype "passive"))
      (node (ref "R49") (pin "2") (pinfunction "2_2") (pintype "passive"))
    )
    (net (code "71") (name "Net-(D8-2)") (class "Default")
      (node (ref "D8") (pin "K") (pinfunction "2_K") (pintype "passive"))
      (node (ref "J4") (pin "2") (pinfunction "-_2") (pintype "passive"))
      (node (ref "Q1") (pin "3") (pinfunction "D_3") (pintype "input"))
    )
    (net (code "72") (name "Net-(D9-1)") (class "Default")
      (node (ref "D9") (pin "A") (pinfunction "1_A") (pintype "passive"))
      (node (ref "R50") (pin "2") (pinfunction "2_2") (pintype "passive"))
    )
    (net (code "73") (name "Net-(D9-2)") (class "Default")
      (node (ref "D9") (pin "K") (pinfunction "2_K") (pintype "passive"))
      (node (ref "J4") (pin "4") (pinfunction "-_4") (pintype "passive"))
      (node (ref "Q2") (pin "3") (pinfunction "D_3") (pintype "input"))
    )
    (net (code "74") (name "Net-(D11-1)") (class "Default")
      (node (ref "D11") (pin "A") (pinfunction "1_A") (pintype "passive"))
      (node (ref "R51") (pin "2") (pinfunction "2_2") (pintype "passive"))
    )
    (net (code "75") (name "Net-(D11-2)") (class "Default")
      (node (ref "D11") (pin "K") (pinfunction "2_K") (pintype "passive"))
      (node (ref "FAN") (pin "1") (pinfunction "1_1") (pintype "passive"))
      (node (ref "J5") (pin "1") (pinfunction "1_1") (pintype "passive"))
      (node (ref "Q3") (pin "3") (pinfunction "C_3") (pintype "passive"))
    )
    (net (code "76") (name "Net-(J2-D+)") (class "Default")
      (node (ref "J2") (pin "3") (pinfunction "D+_3") (pintype "passive"))
      (node (ref "R17") (pin "2") (pinfunction "2_2") (pintype "passive"))
    )
    (net (code "77") (name "Net-(J2-D-)") (class "Default")
      (node (ref "J2") (pin "2") (pinfunction "D-_2") (pintype "passive"))
      (node (ref "R16") (pin "2") (pinfunction "2_2") (pintype "passive"))
    )
    (net (code "78") (name "Net-(J2-PAD)") (class "Default")
      (node (ref "C34") (pin "2") (pinfunction "2_2") (pintype "passive"))
      (node (ref "J2") (pin "6") (pinfunction "PAD_6") (pintype "passive"))
    )
    (net (code "79") (name "Net-(J2-VBUS)") (class "Default")
      (node (ref "J13") (pin "1") (pinfunction "1_1") (pintype "passive"))
      (node (ref "J2") (pin "1") (pinfunction "VBUS_1") (pintype "passive"))
    )
    (net (code "80") (name "Net-(JM1---Pad2)") (class "Default")
      (node (ref "JM1") (pin "2") (pinfunction "-_2") (pintype "passive"))
      (node (ref "TMC1") (pin "26") (pinfunction "OA2_26") (pintype "passive"))
    )
    (net (code "81") (name "Net-(JM1---Pad4)") (class "Default")
      (node (ref "JM1") (pin "4") (pinfunction "-_4") (pintype "passive"))
      (node (ref "TMC1") (pin "21") (pinfunction "OA2_21") (pintype "passive"))
    )
    (net (code "82") (name "Net-(JM2---Pad2)") (class "Default")
      (node (ref "JM2") (pin "2") (pinfunction "-_2") (pintype "passive"))
      (node (ref "TMC2") (pin "26") (pinfunction "OA2_26") (pintype "passive"))
    )
    (net (code "83") (name "Net-(JM2---Pad4)") (class "Default")
      (node (ref "JM2") (pin "4") (pinfunction "-_4") (pintype "passive"))
      (node (ref "TMC2") (pin "21") (pinfunction "OA2_21") (pintype "passive"))
    )
    (net (code "84") (name "Net-(JM3---Pad2)") (class "Default")
      (node (ref "JM3") (pin "2") (pinfunction "-_2") (pintype "passive"))
      (node (ref "JM3_1") (pin "2") (pinfunction "-_2") (pintype "passive"))
      (node (ref "TMC3") (pin "26") (pinfunction "OA2_26") (pintype "passive"))
    )
    (net (code "85") (name "Net-(JM3---Pad4)") (class "Default")
      (node (ref "JM3") (pin "4") (pinfunction "-_4") (pintype "passive"))
      (node (ref "JM3_1") (pin "4") (pinfunction "-_4") (pintype "passive"))
      (node (ref "TMC3") (pin "21") (pinfunction "OA2_21") (pintype "passive"))
    )
    (net (code "86") (name "Net-(JM4---Pad2)") (class "Default")
      (node (ref "JM4") (pin "2") (pinfunction "-_2") (pintype "passive"))
      (node (ref "TMC4") (pin "26") (pinfunction "OA2_26") (pintype "passive"))
    )
    (net (code "87") (name "Net-(JM4---Pad4)") (class "Default")
      (node (ref "JM4") (pin "4") (pinfunction "-_4") (pintype "passive"))
      (node (ref "TMC4") (pin "21") (pinfunction "OA2_21") (pintype "passive"))
    )
    (net (code "88") (name "Net-(POWER--)") (class "Default")
      (node (ref "F1") (pin "1") (pinfunction "+_1") (pintype "passive"))
      (node (ref "F2") (pin "1") (pinfunction "+_1") (pintype "passive"))
      (node (ref "POWER") (pin "1") (pinfunction "-_1") (pintype "passive"))
    )
    (net (code "89") (name "Net-(Q1-G)") (class "Default")
      (node (ref "Q1") (pin "1") (pinfunction "G_1") (pintype "input"))
      (node (ref "R24") (pin "1") (pinfunction "1_1") (pintype "passive"))
    )
    (net (code "90") (name "Net-(Q2-G)") (class "Default")
      (node (ref "Q2") (pin "1") (pinfunction "G_1") (pintype "input"))
      (node (ref "R25") (pin "1") (pinfunction "1_1") (pintype "passive"))
    )
    (net (code "91") (name "Net-(Q3-B)") (class "Default")
      (node (ref "Q3") (pin "2") (pinfunction "B_2") (pintype "passive"))
      (node (ref "R40") (pin "1") (pinfunction "1_1") (pintype "passive"))
    )
    (net (code "92") (name "Net-(TMC1-5VOUT)") (class "Default")
      (node (ref "CC5") (pin "1") (pinfunction "1_1") (pintype "passive"))
      (node (ref "TMC1") (pin "8") (pinfunction "5VOUT_8") (pintype "passive"))
    )
    (net (code "93") (name "Net-(TMC1-BRA)") (class "Default")
      (node (ref "RR2") (pin "1") (pinfunction "1_1") (pintype "passive"))
      (node (ref "TMC1") (pin "23") (pinfunction "BRA_23") (pintype "passive"))
    )
    (net (code "94") (name "Net-(TMC1-BRB)") (class "Default")
      (node (ref "RR1") (pin "1") (pinfunction "1_1") (pintype "passive"))
      (node (ref "TMC1") (pin "27") (pinfunction "BRB_27") (pintype "passive"))
    )
    (net (code "95") (name "Net-(TMC1-CLK)") (class "Default")
      (node (ref "RR4") (pin "2") (pinfunction "2_2") (pintype "passive"))
      (node (ref "TMC1") (pin "13") (pinfunction "CLK_13") (pintype "passive"))
    )
    (net (code "96") (name "Net-(TMC1-CPI)") (class "Default")
      (node (ref "CC3") (pin "1") (pinfunction "1_1") (pintype "passive"))
      (node (ref "TMC1") (pin "5") (pinfunction "CPI_5") (pintype "passive"))
    )
    (net (code "97") (name "Net-(TMC1-CPO)") (class "Default")
      (node (ref "CC3") (pin "2") (pinfunction "2_2") (pintype "passive"))
      (node (ref "TMC1") (pin "4") (pinfunction "CPO_4") (pintype "passive"))
    )
    (net (code "98") (name "Net-(TMC1-DIAG)") (class "Default")
      (node (ref "JC1") (pin "1") (pinfunction "1_1") (pintype "passive"))
      (node (ref "TMC1") (pin "11") (pinfunction "DIAG_11") (pintype "passive"))
    )
    (net (code "99") (name "Net-(TMC1-OA1)") (class "Default")
      (node (ref "JM1") (pin "3") (pinfunction "+_3") (pintype "passive"))
      (node (ref "TMC1") (pin "24") (pinfunction "OA1_24") (pintype "passive"))
    )
    (net (code "100") (name "Net-(TMC1-OB2)") (class "Default")
      (node (ref "JM1") (pin "1") (pinfunction "+_1") (pintype "passive"))
      (node (ref "TMC1") (pin "1") (pinfunction "OB2_1") (pintype "passive"))
    )
    (net (code "101") (name "Net-(TMC1-SPREAD)") (class "Default")
      (node (ref "JJ1") (pin "2") (pinfunction "2_2") (pintype "passive"))
      (node (ref "TMC1") (pin "7") (pinfunction "SPREAD_7") (pintype "passive"))
    )
    (net (code "102") (name "Net-(TMC1-VCP)") (class "Default")
      (node (ref "CC4") (pin "1") (pinfunction "1_1") (pintype "passive"))
      (node (ref "TMC1") (pin "6") (pinfunction "VCP_6") (pintype "passive"))
    )
    (net (code "103") (name "Net-(TMC2-5VOUT)") (class "Default")
      (node (ref "CC10") (pin "1") (pinfunction "1_1") (pintype "passive"))
      (node (ref "TMC2") (pin "8") (pinfunction "5VOUT_8") (pintype "passive"))
    )
    (net (code "104") (name "Net-(TMC2-BRA)") (class "Default")
      (node (ref "RR7") (pin "1") (pinfunction "1_1") (pintype "passive"))
      (node (ref "TMC2") (pin "23") (pinfunction "BRA_23") (pintype "passive"))
    )
    (net (code "105") (name "Net-(TMC2-BRB)") (class "Default")
      (node (ref "RR6") (pin "1") (pinfunction "1_1") (pintype "passive"))
      (node (ref "TMC2") (pin "27") (pinfunction "BRB_27") (pintype "passive"))
    )
    (net (code "106") (name "Net-(TMC2-CLK)") (class "Default")
      (node (ref "RR9") (pin "2") (pinfunction "2_2") (pintype "passive"))
      (node (ref "TMC2") (pin "13") (pinfunction "CLK_13") (pintype "passive"))
    )
    (net (code "107") (name "Net-(TMC2-CPI)") (class "Default")
      (node (ref "CC8") (pin "1") (pinfunction "1_1") (pintype "passive"))
      (node (ref "TMC2") (pin "5") (pinfunction "CPI_5") (pintype "passive"))
    )
    (net (code "108") (name "Net-(TMC2-CPO)") (class "Default")
      (node (ref "CC8") (pin "2") (pinfunction "2_2") (pintype "passive"))
      (node (ref "TMC2") (pin "4") (pinfunction "CPO_4") (pintype "passive"))
    )
    (net (code "109") (name "Net-(TMC2-DIAG)") (class "Default")
      (node (ref "JC2") (pin "1") (pinfunction "1_1") (pintype "passive"))
      (node (ref "TMC2") (pin "11") (pinfunction "DIAG_11") (pintype "passive"))
    )
    (net (code "110") (name "Net-(TMC2-OA1)") (class "Default")
      (node (ref "JM2") (pin "3") (pinfunction "+_3") (pintype "passive"))
      (node (ref "TMC2") (pin "24") (pinfunction "OA1_24") (pintype "passive"))
    )
    (net (code "111") (name "Net-(TMC2-OB2)") (class "Default")
      (node (ref "JM2") (pin "1") (pinfunction "+_1") (pintype "passive"))
      (node (ref "TMC2") (pin "1") (pinfunction "OB2_1") (pintype "passive"))
    )
    (net (code "112") (name "Net-(TMC2-SPREAD)") (class "Default")
      (node (ref "JJ2") (pin "2") (pinfunction "2_2") (pintype "passive"))
      (node (ref "TMC2") (pin "7") (pinfunction "SPREAD_7") (pintype "passive"))
    )
    (net (code "113") (name "Net-(TMC2-VCP)") (class "Default")
      (node (ref "CC9") (pin "1") (pinfunction "1_1") (pintype "passive"))
      (node (ref "TMC2") (pin "6") (pinfunction "VCP_6") (pintype "passive"))
    )
    (net (code "114") (name "Net-(TMC3-5VOUT)") (class "Default")
      (node (ref "CC15") (pin "1") (pinfunction "1_1") (pintype "passive"))
      (node (ref "TMC3") (pin "8") (pinfunction "5VOUT_8") (pintype "passive"))
    )
    (net (code "115") (name "Net-(TMC3-BRA)") (class "Default")
      (node (ref "RR12") (pin "1") (pinfunction "1_1") (pintype "passive"))
      (node (ref "TMC3") (pin "23") (pinfunction "BRA_23") (pintype "passive"))
    )
    (net (code "116") (name "Net-(TMC3-BRB)") (class "Default")
      (node (ref "RR11") (pin "1") (pinfunction "1_1") (pintype "passive"))
      (node (ref "TMC3") (pin "27") (pinfunction "BRB_27") (pintype "passive"))
    )
    (net (code "117") (name "Net-(TMC3-CLK)") (class "Default")
      (node (ref "RR14") (pin "2") (pinfunction "2_2") (pintype "passive"))
      (node (ref "TMC3") (pin "13") (pinfunction "CLK_13") (pintype "passive"))
    )
    (net (code "118") (name "Net-(TMC3-CPI)") (class "Default")
      (node (ref "CC13") (pin "1") (pinfunction "1_1") (pintype "passive"))
      (node (ref "TMC3") (pin "5") (pinfunction "CPI_5") (pintype "passive"))
    )
    (net (code "119") (name "Net-(TMC3-CPO)") (class "Default")
      (node (ref "CC13") (pin "2") (pinfunction "2_2") (pintype "passive"))
      (node (ref "TMC3") (pin "4") (pinfunction "CPO_4") (pintype "passive"))
    )
    (net (code "120") (name "Net-(TMC3-DIAG)") (class "Default")
      (node (ref "JC3") (pin "1") (pinfunction "1_1") (pintype "passive"))
      (node (ref "TMC3") (pin "11") (pinfunction "DIAG_11") (pintype "passive"))
    )
    (net (code "121") (name "Net-(TMC3-OA1)") (class "Default")
      (node (ref "JM3") (pin "3") (pinfunction "+_3") (pintype "passive"))
      (node (ref "JM3_1") (pin "3") (pinfunction "+_3") (pintype "passive"))
      (node (ref "TMC3") (pin "24") (pinfunction "OA1_24") (pintype "passive"))
    )
    (net (code "122") (name "Net-(TMC3-OB2)") (class "Default")
      (node (ref "JM3") (pin "1") (pinfunction "+_1") (pintype "passive"))
      (node (ref "JM3_1") (pin "1") (pinfunction "+_1") (pintype "passive"))
      (node (ref "TMC3") (pin "1") (pinfunction "OB2_1") (pintype "passive"))
    )
    (net (code "123") (name "Net-(TMC3-SPREAD)") (class "Default")
      (node (ref "JJ3") (pin "2") (pinfunction "2_2") (pintype "passive"))
      (node (ref "TMC3") (pin "7") (pinfunction "SPREAD_7") (pintype "passive"))
    )
    (net (code "124") (name "Net-(TMC3-VCP)") (class "Default")
      (node (ref "CC14") (pin "1") (pinfunction "1_1") (pintype "passive"))
      (node (ref "TMC3") (pin "6") (pinfunction "VCP_6") (pintype "passive"))
    )
    (net (code "125") (name "Net-(TMC4-5VOUT)") (class "Default")
      (node (ref "CC20") (pin "1") (pinfunction "1_1") (pintype "passive"))
      (node (ref "TMC4") (pin "8") (pinfunction "5VOUT_8") (pintype "passive"))
    )
    (net (code "126") (name "Net-(TMC4-BRA)") (class "Default")
      (node (ref "RR17") (pin "1") (pinfunction "1_1") (pintype "passive"))
      (node (ref "TMC4") (pin "23") (pinfunction "BRA_23") (pintype "passive"))
    )
    (net (code "127") (name "Net-(TMC4-BRB)") (class "Default")
      (node (ref "RR16") (pin "1") (pinfunction "1_1") (pintype "passive"))
      (node (ref "TMC4") (pin "27") (pinfunction "BRB_27") (pintype "passive"))
    )
    (net (code "128") (name "Net-(TMC4-CLK)") (class "Default")
      (node (ref "RR19") (pin "2") (pinfunction "2_2") (pintype "passive"))
      (node (ref "TMC4") (pin "13") (pinfunction "CLK_13") (pintype "passive"))
    )
    (net (code "129") (name "Net-(TMC4-CPI)") (class "Default")
      (node (ref "CC18") (pin "1") (pinfunction "1_1") (pintype "passive"))
      (node (ref "TMC4") (pin "5") (pinfunction "CPI_5") (pintype "passive"))
    )
    (net (code "130") (name "Net-(TMC4-CPO)") (class "Default")
      (node (ref "CC18") (pin "2") (pinfunction "2_2") (pintype "passive"))
      (node (ref "TMC4") (pin "4") (pinfunction "CPO_4") (pintype "passive"))
    )
    (net (code "131") (name "Net-(TMC4-DIAG)") (class "Default")
      (node (ref "JC4") (pin "1") (pinfunction "1_1") (pintype "passive"))
      (node (ref "TMC4") (pin "11") (pinfunction "DIAG_11") (pintype "passive"))
    )
    (net (code "132") (name "Net-(TMC4-OA1)") (class "Default")
      (node (ref "JM4") (pin "3") (pinfunction "+_3") (pintype "passive"))
      (node (ref "TMC4") (pin "24") (pinfunction "OA1_24") (pintype "passive"))
    )
    (net (code "133") (name "Net-(TMC4-OB2)") (class "Default")
      (node (ref "JM4") (pin "1") (pinfunction "+_1") (pintype "passive"))
      (node (ref "TMC4") (pin "1") (pinfunction "OB2_1") (pintype "passive"))
    )
    (net (code "134") (name "Net-(TMC4-SPREAD)") (class "Default")
      (node (ref "JJ4") (pin "2") (pinfunction "2_2") (pintype "passive"))
      (node (ref "TMC4") (pin "7") (pinfunction "SPREAD_7") (pintype "passive"))
    )
    (net (code "135") (name "Net-(TMC4-VCP)") (class "Default")
      (node (ref "CC19") (pin "1") (pinfunction "1_1") (pintype "passive"))
      (node (ref "TMC4") (pin "6") (pinfunction "VCP_6") (pintype "passive"))
    )
    (net (code "136") (name "Net-(U1-BST)") (class "Default")
      (node (ref "C3") (pin "1") (pinfunction "1_1") (pintype "passive"))
      (node (ref "U1") (pin "8") (pinfunction "BST_8") (pintype "passive"))
    )
    (net (code "137") (name "Net-(U1-COMP)") (class "Default")
      (node (ref "C9") (pin "1") (pinfunction "1_1") (pintype "passive"))
      (node (ref "U1") (pin "3") (pinfunction "COMP_3") (pintype "passive"))
    )
    (net (code "138") (name "Net-(U1-EN)") (class "Default")
      (node (ref "R2") (pin "1") (pinfunction "1_1") (pintype "passive"))
      (node (ref "R5") (pin "2") (pinfunction "2_2") (pintype "passive"))
      (node (ref "U1") (pin "2") (pinfunction "EN_2") (pintype "passive"))
    )
    (net (code "139") (name "Net-(U1-FB)") (class "Default")
      (node (ref "R3") (pin "2") (pinfunction "2_2") (pintype "passive"))
      (node (ref "R4") (pin "2") (pinfunction "2_2") (pintype "passive"))
      (node (ref "U1") (pin "4") (pinfunction "FB_4") (pintype "passive"))
    )
    (net (code "140") (name "Net-(U1-FREQ)") (class "Default")
      (node (ref "R6") (pin "2") (pinfunction "2_2") (pintype "passive"))
      (node (ref "U1") (pin "6") (pinfunction "FREQ_6") (pintype "passive"))
    )
    (net (code "141") (name "Net-(U3-PC14{slash}OSC32_IN)") (class "Default")
      (node (ref "C18") (pin "2") (pinfunction "2_2") (pintype "passive"))
      (node (ref "U3") (pin "3") (pinfunction "PC14/OSC32_IN_3") (pintype "passive"))
      (node (ref "Y2") (pin "1") (pinfunction "OSC1_1") (pintype "passive"))
    )
    (net (code "142") (name "Net-(U3-PC15{slash}OSC32_OUT)") (class "Default")
      (node (ref "C17") (pin "2") (pinfunction "2_2") (pintype "passive"))
      (node (ref "U3") (pin "4") (pinfunction "PC15/OSC32_OUT_4") (pintype "passive"))
      (node (ref "Y2") (pin "2") (pinfunction "OSC2_2") (pintype "passive"))
    )
    (net (code "143") (name "Net-(U3-PD0{slash}OSC_IN)") (class "Default")
      (node (ref "C16") (pin "2") (pinfunction "2_2") (pintype "passive"))
      (node (ref "U3") (pin "5") (pinfunction "PD0/OSC_IN_5") (pintype "passive"))
      (node (ref "Y1") (pin "1") (pinfunction "OSC1_1") (pintype "passive"))
    )
    (net (code "144") (name "Net-(U3-PD1{slash}OSC_OUT)") (class "Default")
      (node (ref "C15") (pin "2") (pinfunction "2_2") (pintype "passive"))
      (node (ref "U3") (pin "6") (pinfunction "PD1/OSC_OUT_6") (pintype "passive"))
      (node (ref "Y1") (pin "2") (pinfunction "OSC2_2") (pintype "passive"))
    )
    (net (code "145") (name "Net-(U4-DTR)") (class "Default")
      (node (ref "C21") (pin "1") (pinfunction "1_1") (pintype "passive"))
      (node (ref "U4") (pin "13") (pinfunction "DTR_13") (pintype "passive"))
    )
    (net (code "146") (name "Net-(U4-RX)") (class "Default")
      (node (ref "R15") (pin "1") (pinfunction "1_1") (pintype "passive"))
      (node (ref "U4") (pin "3") (pinfunction "RX_3") (pintype "passive"))
    )
    (net (code "147") (name "Net-(U4-TX)") (class "Default")
      (node (ref "R14") (pin "1") (pinfunction "1_1") (pintype "passive"))
      (node (ref "U4") (pin "2") (pinfunction "TX_2") (pintype "passive"))
    )
    (net (code "148") (name "Net-(U4-VCC)") (class "Default")
      (node (ref "C20") (pin "2") (pinfunction "2_2") (pintype "passive"))
      (node (ref "U4") (pin "16") (pinfunction "VCC_16") (pintype "passive"))
    )
    (net (code "149") (name "U5V") (class "Default")
      (node (ref "C22") (pin "1") (pinfunction "1_1") (pintype "passive"))
      (node (ref "D5") (pin "1") (pinfunction "A_1") (pintype "passive"))
      (node (ref "J13") (pin "2") (pinfunction "2_2") (pintype "passive"))
    )
    (net (code "150") (name "VCC") (class "Default")
      (node (ref "AUX-1") (pin "1") (pinfunction "1_1") (pintype "passive"))
      (node (ref "AUX-1") (pin "2") (pinfunction "2_2") (pintype "passive"))
      (node (ref "C7") (pin "1") (pinfunction "1_1") (pintype "passive"))
      (node (ref "D5") (pin "2") (pinfunction "K_2") (pintype "passive"))
      (node (ref "EXP1") (pin "10") (pinfunction "10_10") (pintype "passive"))
      (node (ref "F3") (pin "2") (pinfunction "+_2") (pintype "passive"))
      (node (ref "J10") (pin "1") (pinfunction "1_1") (pintype "passive"))
      (node (ref "J18") (pin "1") (pinfunction "1_1") (pintype "passive"))
      (node (ref "J6") (pin "2") (pinfunction "2_2") (pintype "passive"))
      (node (ref "MT_DET") (pin "1") (pinfunction "1_1") (pintype "passive"))
      (node (ref "U2") (pin "3") (pinfunction "VI_3") (pintype "passive"))
    )
    (net (code "151") (name "unconnected-(AUX-1-Pad5)") (class "Default")
      (node (ref "AUX-1") (pin "5") (pinfunction "5_5") (pintype "passive"))
    )
    (net (code "152") (name "unconnected-(AUX-1-Pad7)") (class "Default")
      (node (ref "AUX-1") (pin "7") (pinfunction "7_7") (pintype "passive"))
    )
    (net (code "153") (name "unconnected-(EXP2-Pad10)") (class "Default")
      (node (ref "EXP2") (pin "10") (pinfunction "10_10") (pintype "passive"))
    )
    (net (code "154") (name "unconnected-(J2-ID-Pad4)") (class "Default")
      (node (ref "J2") (pin "4") (pinfunction "ID_4") (pintype "passive"))
    )
    (net (code "155") (name "unconnected-(J13-Pad3)") (class "Default")
      (node (ref "J13") (pin "3") (pinfunction "3_3") (pintype "passive"))
    )
    (net (code "156") (name "unconnected-(TMC1-INDEX-Pad12)") (class "Default")
      (node (ref "TMC1") (pin "12") (pinfunction "INDEX_12") (pintype "passive"))
    )
    (net (code "157") (name "unconnected-(TMC1-MS1{slash}AD0-Pad9)") (class "Default")
      (node (ref "TMC1") (pin "9") (pinfunction "MS1/AD0_9") (pintype "passive"))
    )
    (net (code "158") (name "unconnected-(TMC1-MS2{slash}AD2-Pad10)") (class "Default")
      (node (ref "TMC1") (pin "10") (pinfunction "MS2/AD2_10") (pintype "passive"))
    )
    (net (code "159") (name "unconnected-(TMC1-NC-Pad25)") (class "Default")
      (node (ref "TMC1") (pin "25") (pinfunction "NC_25") (pintype "passive"))
    )
    (net (code "160") (name "unconnected-(TMC1-STDBY-Pad20)") (class "Default")
      (node (ref "TMC1") (pin "20") (pinfunction "STDBY_20") (pintype "passive"))
    )
    (net (code "161") (name "unconnected-(TMC1-VREF-Pad17)") (class "Default")
      (node (ref "TMC1") (pin "17") (pinfunction "VREF_17") (pintype "passive"))
    )
    (net (code "162") (name "unconnected-(TMC2-INDEX-Pad12)") (class "Default")
      (node (ref "TMC2") (pin "12") (pinfunction "INDEX_12") (pintype "passive"))
    )
    (net (code "163") (name "unconnected-(TMC2-MS1{slash}AD0-Pad9)") (class "Default")
      (node (ref "TMC2") (pin "9") (pinfunction "MS1/AD0_9") (pintype "passive"))
    )
    (net (code "164") (name "unconnected-(TMC2-MS2{slash}AD2-Pad10)") (class "Default")
      (node (ref "TMC2") (pin "10") (pinfunction "MS2/AD2_10") (pintype "passive"))
    )
    (net (code "165") (name "unconnected-(TMC2-NC-Pad25)") (class "Default")
      (node (ref "TMC2") (pin "25") (pinfunction "NC_25") (pintype "passive"))
    )
    (net (code "166") (name "unconnected-(TMC2-STDBY-Pad20)") (class "Default")
      (node (ref "TMC2") (pin "20") (pinfunction "STDBY_20") (pintype "passive"))
    )
    (net (code "167") (name "unconnected-(TMC2-VREF-Pad17)") (class "Default")
      (node (ref "TMC2") (pin "17") (pinfunction "VREF_17") (pintype "passive"))
    )
    (net (code "168") (name "unconnected-(TMC3-INDEX-Pad12)") (class "Default")
      (node (ref "TMC3") (pin "12") (pinfunction "INDEX_12") (pintype "passive"))
    )
    (net (code "169") (name "unconnected-(TMC3-MS1{slash}AD0-Pad9)") (class "Default")
      (node (ref "TMC3") (pin "9") (pinfunction "MS1/AD0_9") (pintype "passive"))
    )
    (net (code "170") (name "unconnected-(TMC3-MS2{slash}AD2-Pad10)") (class "Default")
      (node (ref "TMC3") (pin "10") (pinfunction "MS2/AD2_10") (pintype "passive"))
    )
    (net (code "171") (name "unconnected-(TMC3-NC-Pad25)") (class "Default")
      (node (ref "TMC3") (pin "25") (pinfunction "NC_25") (pintype "passive"))
    )
    (net (code "172") (name "unconnected-(TMC3-STDBY-Pad20)") (class "Default")
      (node (ref "TMC3") (pin "20") (pinfunction "STDBY_20") (pintype "passive"))
    )
    (net (code "173") (name "unconnected-(TMC3-VREF-Pad17)") (class "Default")
      (node (ref "TMC3") (pin "17") (pinfunction "VREF_17") (pintype "passive"))
    )
    (net (code "174") (name "unconnected-(TMC4-INDEX-Pad12)") (class "Default")
      (node (ref "TMC4") (pin "12") (pinfunction "INDEX_12") (pintype "passive"))
    )
    (net (code "175") (name "unconnected-(TMC4-MS1{slash}AD0-Pad9)") (class "Default")
      (node (ref "TMC4") (pin "9") (pinfunction "MS1/AD0_9") (pintype "passive"))
    )
    (net (code "176") (name "unconnected-(TMC4-MS2{slash}AD2-Pad10)") (class "Default")
      (node (ref "TMC4") (pin "10") (pinfunction "MS2/AD2_10") (pintype "passive"))
    )
    (net (code "177") (name "unconnected-(TMC4-NC-Pad25)") (class "Default")
      (node (ref "TMC4") (pin "25") (pinfunction "NC_25") (pintype "passive"))
    )
    (net (code "178") (name "unconnected-(TMC4-STDBY-Pad20)") (class "Default")
      (node (ref "TMC4") (pin "20") (pinfunction "STDBY_20") (pintype "passive"))
    )
    (net (code "179") (name "unconnected-(TMC4-VREF-Pad17)") (class "Default")
      (node (ref "TMC4") (pin "17") (pinfunction "VREF_17") (pintype "passive"))
    )
    (net (code "180") (name "unconnected-(U3-VBAT-Pad1)") (class "Default")
      (node (ref "U3") (pin "1") (pinfunction "VBAT_1") (pintype "passive+no_connect"))
    )
    (net (code "181") (name "unconnected-(U4-CTS-Pad9)") (class "Default")
      (node (ref "U4") (pin "9") (pinfunction "CTS_9") (pintype "passive"))
    )
    (net (code "182") (name "unconnected-(U4-DCD-Pad12)") (class "Default")
      (node (ref "U4") (pin "12") (pinfunction "DCD_12") (pintype "passive"))
    )
    (net (code "183") (name "unconnected-(U4-DSR-Pad10)") (class "Default")
      (node (ref "U4") (pin "10") (pinfunction "DSR_10") (pintype "passive"))
    )
    (net (code "184") (name "unconnected-(U4-R232-Pad15)") (class "Default")
      (node (ref "U4") (pin "15") (pinfunction "R232_15") (pintype "passive"))
    )
    (net (code "185") (name "unconnected-(U4-RI-Pad11)") (class "Default")
      (node (ref "U4") (pin "11") (pinfunction "RI_11") (pintype "passive"))
    )
    (net (code "186") (name "unconnected-(U4-RTS-Pad14)") (class "Default")
      (node (ref "U4") (pin "14") (pinfunction "RTS_14") (pintype "passive"))
    )
    (net (code "187") (name "unconnected-(U4-XI-Pad7)") (class "Default")
      (node (ref "U4") (pin "7") (pinfunction "XI_7") (pintype "passive"))
    )
    (net (code "188") (name "unconnected-(U4-XO-Pad8)") (class "Default")
      (node (ref "U4") (pin "8") (pinfunction "XO_8") (pintype "passive"))
    )
  )
)
